# AK4493-Combi10.net
KiCad netlist of a schematic drawn in EAGLE
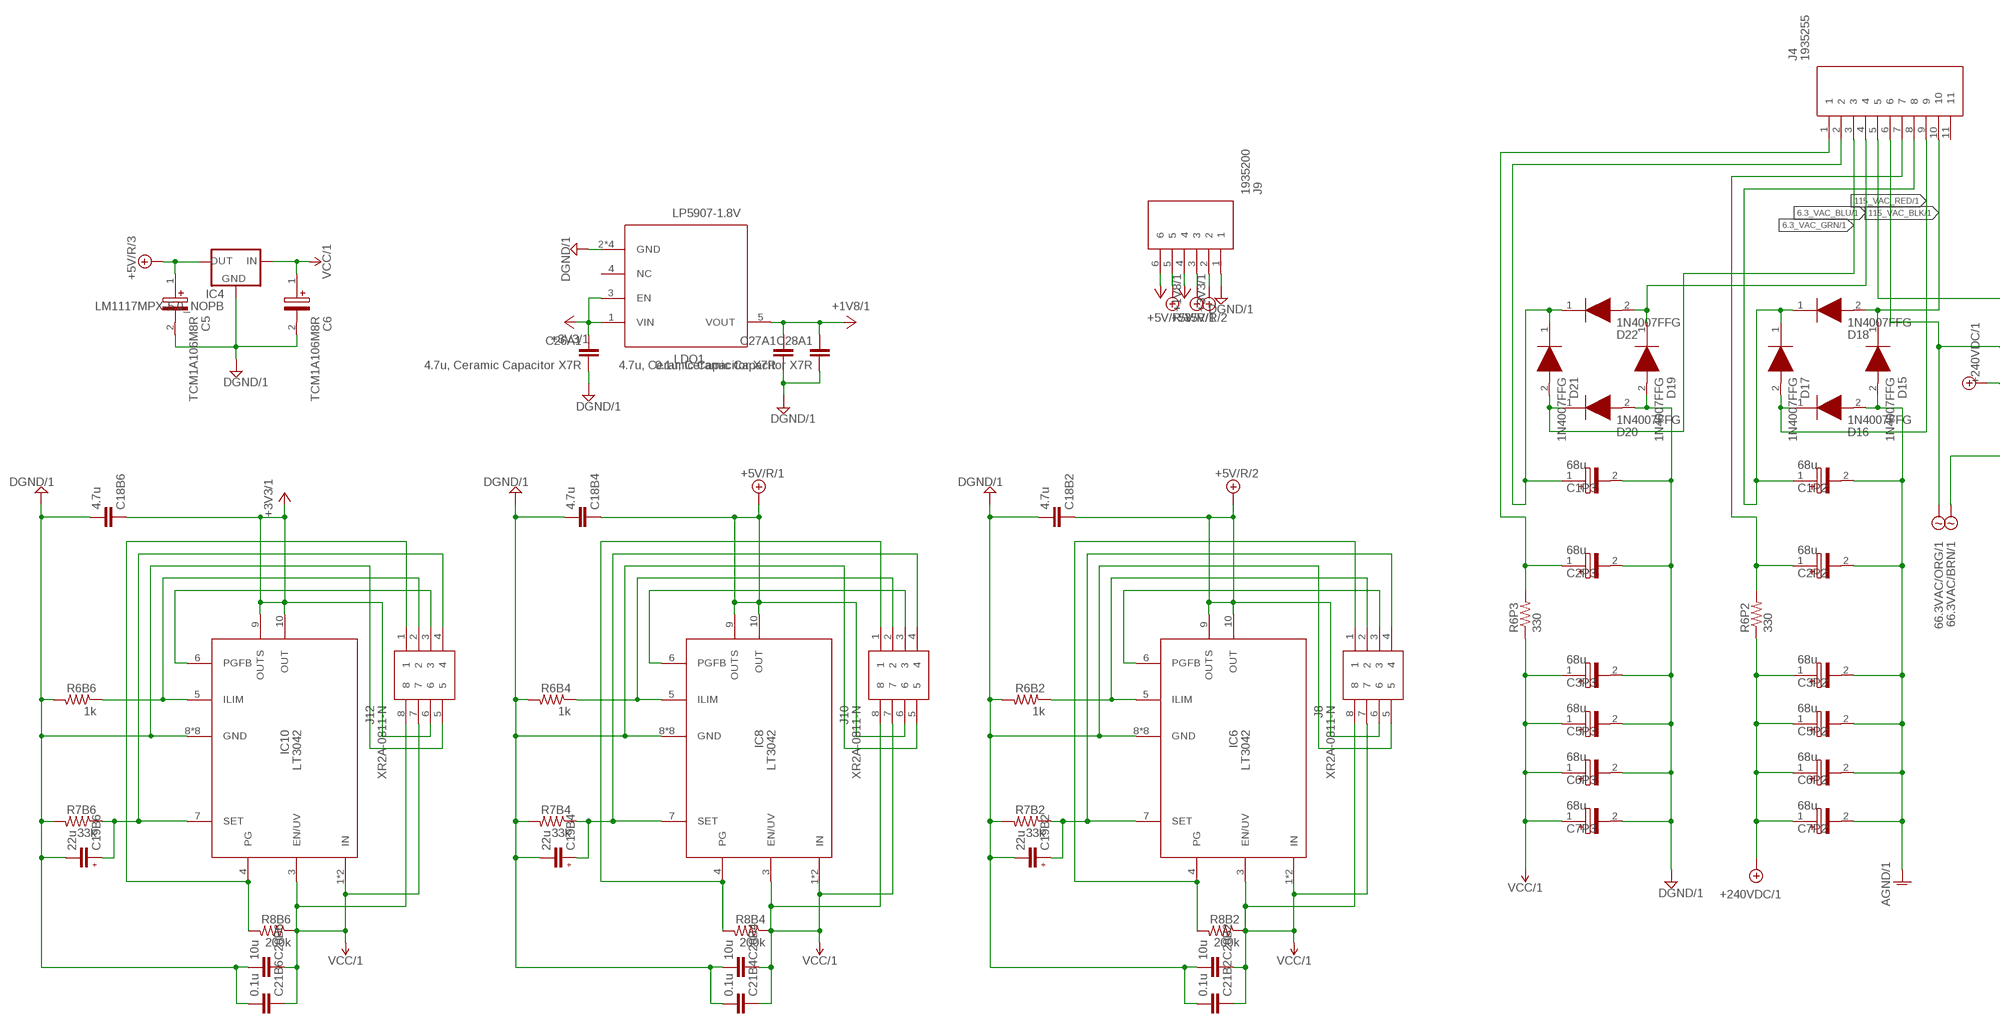
[diagram p0: schematic, sheet 1, part 1 of 3]
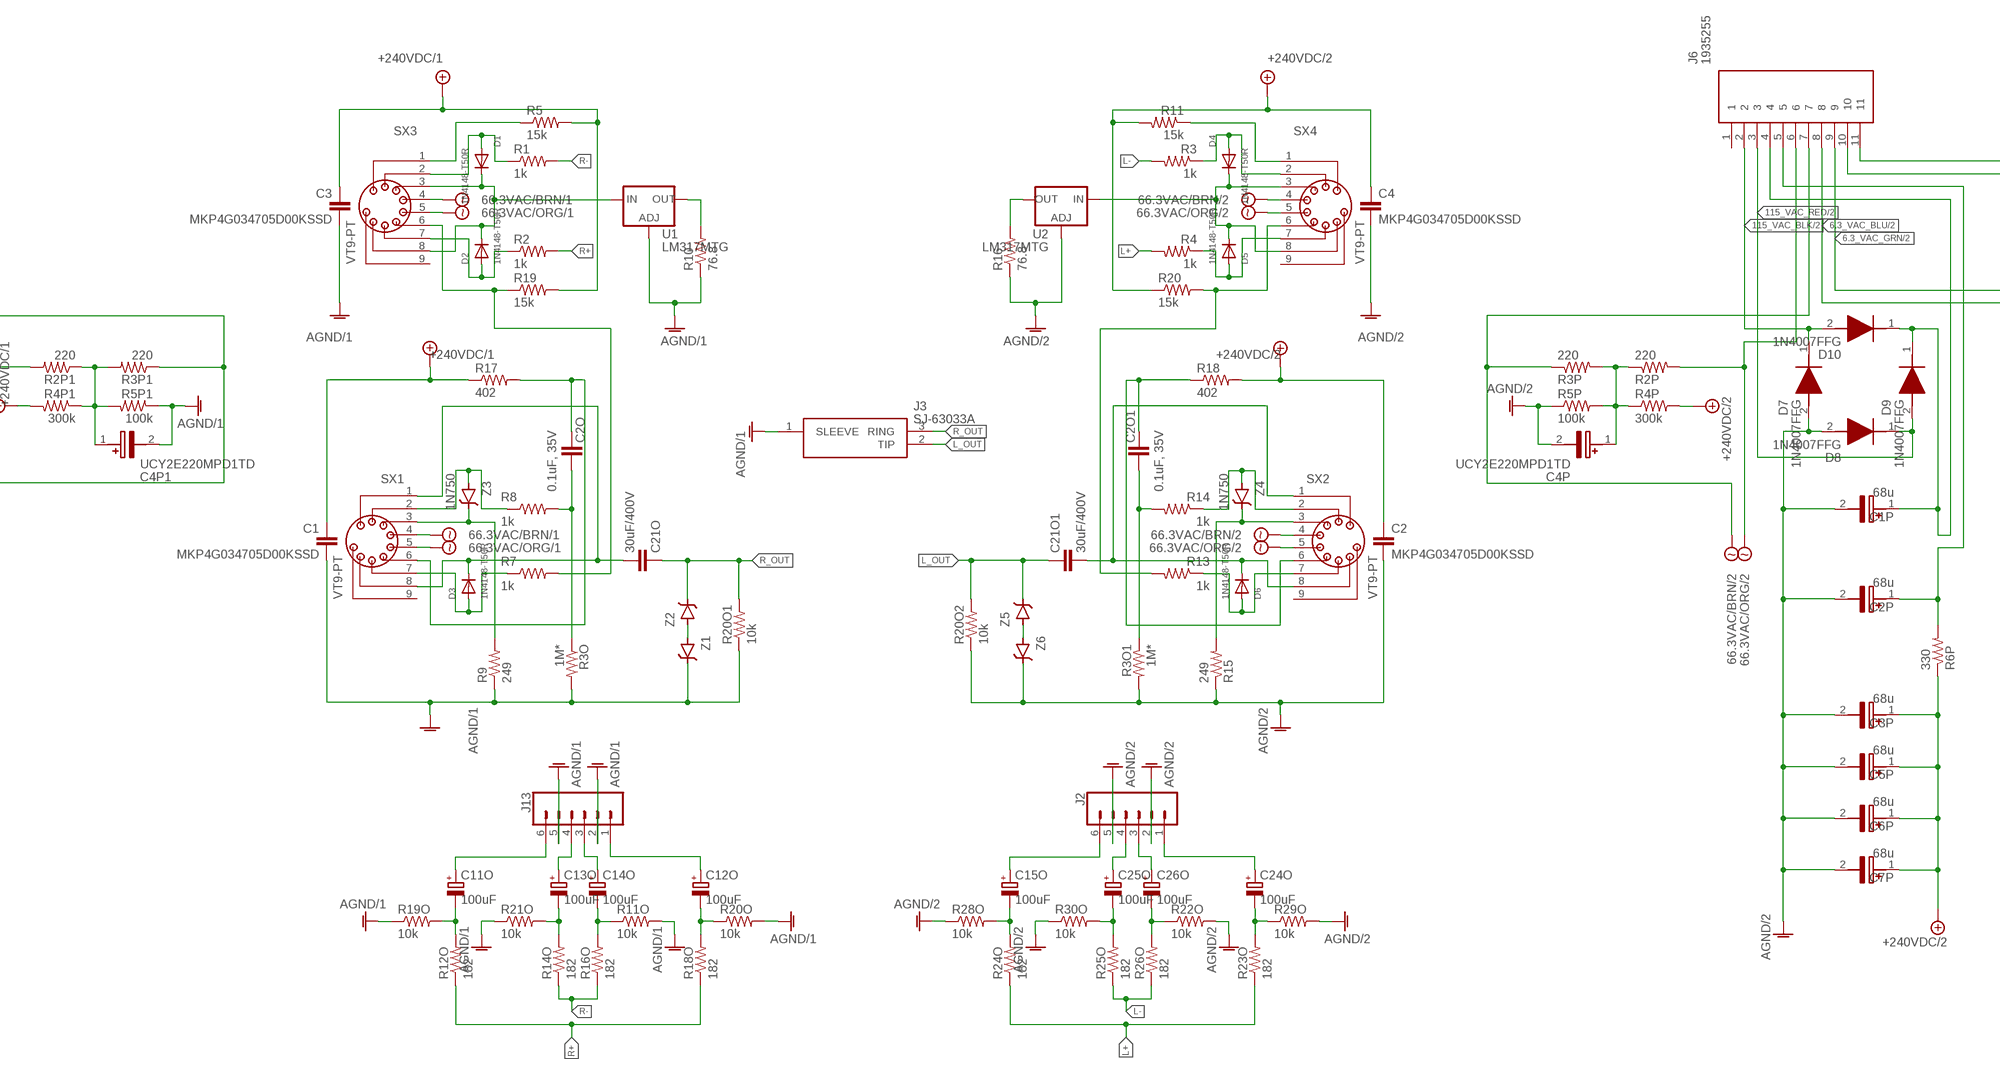
[diagram p1: schematic, sheet 1, part 2 of 3]
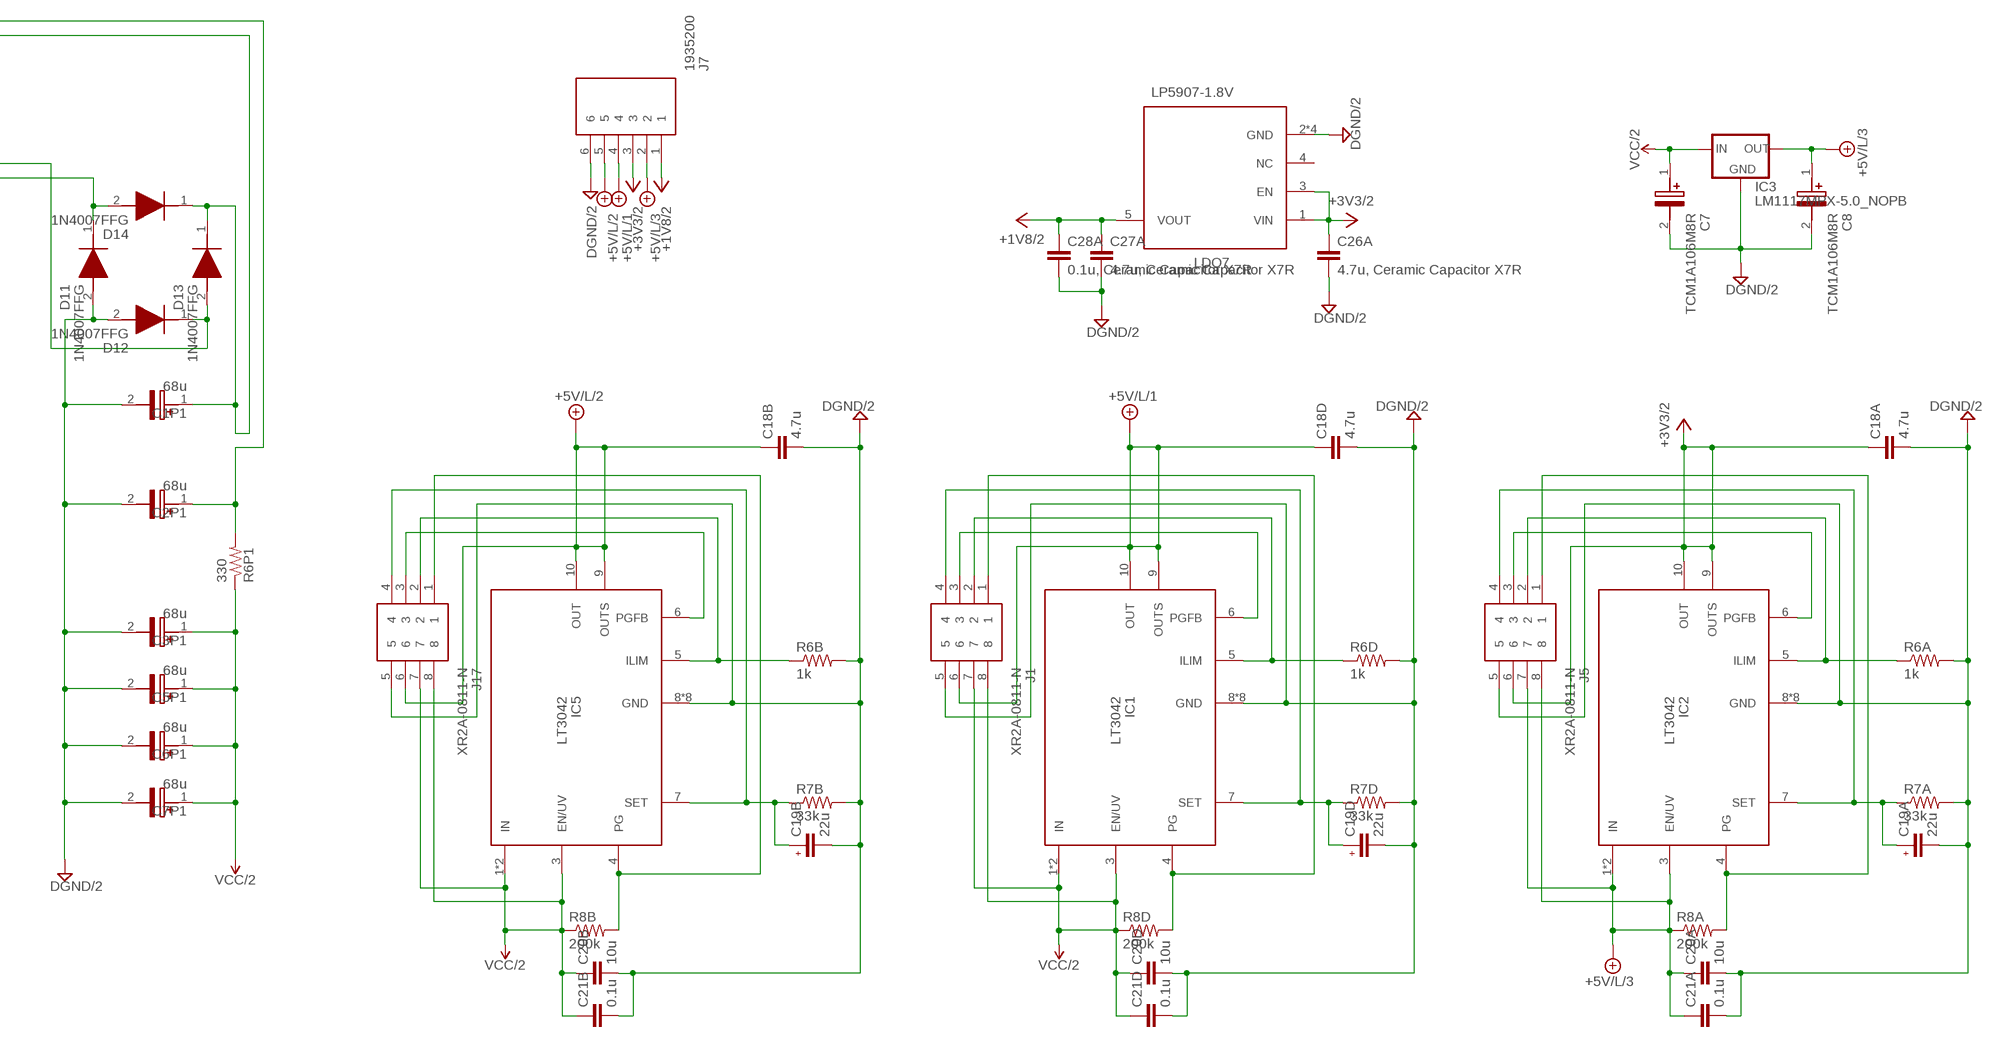
[diagram p2: schematic, sheet 1, part 3 of 3]

(export (version "E")
  (design (tool "Eeschema 10.0.6"))
  (components
    (comp (ref "C1")
      (value "MKP4G034705D00KSSD")
      (footprint "eagle-import:MKP4G034705D00KSSD")
      (fields (field (name "MOUSER_PART_NUMBER") "505-MKP4G034705DKSSD"))
      (libsource (lib "eagle-import") (part "MKP4G034705D00KSSD"))
    )
    (comp (ref "C1P")
      (value "68u")
      (footprint "eagle-import:CAPPRD750W80D1475H4700")
      (fields
        (field (name "MANUFACTURER_PART_NUMBER") "500HXW68MEFR14.5X45")
        (field (name "MOUSER_PART_NUMBER") "232-500HXW68MEFR145X")
      )
      (libsource (lib "eagle-import") (part "500HXW68MEFR14.5X45"))
    )
    (comp (ref "C1P1")
      (value "68u")
      (footprint "eagle-import:CAPPRD750W80D1475H4700")
      (fields
        (field (name "MANUFACTURER_PART_NUMBER") "500HXW68MEFR14.5X45")
        (field (name "MOUSER_PART_NUMBER") "232-500HXW68MEFR145X")
      )
      (libsource (lib "eagle-import") (part "500HXW68MEFR14.5X45"))
    )
    (comp (ref "C1P2")
      (value "68u")
      (footprint "eagle-import:CAPPRD750W80D1475H4700")
      (fields
        (field (name "MANUFACTURER_PART_NUMBER") "500HXW68MEFR14.5X45")
        (field (name "MOUSER_PART_NUMBER") "232-500HXW68MEFR145X")
      )
      (libsource (lib "eagle-import") (part "500HXW68MEFR14.5X45"))
    )
    (comp (ref "C1P3")
      (value "68u")
      (footprint "eagle-import:CAPPRD750W80D1475H4700")
      (fields
        (field (name "MANUFACTURER_PART_NUMBER") "500HXW68MEFR14.5X45")
        (field (name "MOUSER_PART_NUMBER") "232-500HXW68MEFR145X")
      )
      (libsource (lib "eagle-import") (part "500HXW68MEFR14.5X45"))
    )
    (comp (ref "C2")
      (value "MKP4G034705D00KSSD")
      (footprint "eagle-import:MKP4G034705D00KSSD")
      (fields (field (name "MOUSER_PART_NUMBER") "505-MKP4G034705DKSSD"))
      (libsource (lib "eagle-import") (part "MKP4G034705D00KSSD"))
    )
    (comp (ref "C2O")
      (value "0.1uF, 35V")
      (footprint "eagle-import:MKS4B031002A00JC00")
      (fields
        (field (name "MANUFACTURER_PART_NUMBER") "MKS4B031002A00JC00")
        (field (name "MOUSER_PART_NUMBER") "505-MKS4B0312AJC")
      )
      (libsource (lib "eagle-import") (part "MKS4B031002A00JC00"))
    )
    (comp (ref "C2O1")
      (value "0.1uF, 35V")
      (footprint "eagle-import:MKS4B031002A00JC00")
      (fields
        (field (name "MANUFACTURER_PART_NUMBER") "MKS4B031002A00JC00")
        (field (name "MOUSER_PART_NUMBER") "505-MKS4B0312AJC")
      )
      (libsource (lib "eagle-import") (part "MKS4B031002A00JC00"))
    )
    (comp (ref "C2P")
      (value "68u")
      (footprint "eagle-import:CAPPRD750W80D1475H4700")
      (fields
        (field (name "MANUFACTURER_PART_NUMBER") "500HXW68MEFR14.5X45")
        (field (name "MOUSER_PART_NUMBER") "232-500HXW68MEFR145X")
      )
      (libsource (lib "eagle-import") (part "500HXW68MEFR14.5X45"))
    )
    (comp (ref "C2P1")
      (value "68u")
      (footprint "eagle-import:CAPPRD750W80D1475H4700")
      (fields
        (field (name "MANUFACTURER_PART_NUMBER") "500HXW68MEFR14.5X45")
        (field (name "MOUSER_PART_NUMBER") "232-500HXW68MEFR145X")
      )
      (libsource (lib "eagle-import") (part "500HXW68MEFR14.5X45"))
    )
    (comp (ref "C2P2")
      (value "68u")
      (footprint "eagle-import:CAPPRD750W80D1475H4700")
      (fields
        (field (name "MANUFACTURER_PART_NUMBER") "500HXW68MEFR14.5X45")
        (field (name "MOUSER_PART_NUMBER") "232-500HXW68MEFR145X")
      )
      (libsource (lib "eagle-import") (part "500HXW68MEFR14.5X45"))
    )
    (comp (ref "C2P3")
      (value "68u")
      (footprint "eagle-import:CAPPRD750W80D1475H4700")
      (fields
        (field (name "MANUFACTURER_PART_NUMBER") "500HXW68MEFR14.5X45")
        (field (name "MOUSER_PART_NUMBER") "232-500HXW68MEFR145X")
      )
      (libsource (lib "eagle-import") (part "500HXW68MEFR14.5X45"))
    )
    (comp (ref "C3")
      (value "MKP4G034705D00KSSD")
      (footprint "eagle-import:MKP4G034705D00KSSD")
      (fields (field (name "MOUSER_PART_NUMBER") "505-MKP4G034705DKSSD"))
      (libsource (lib "eagle-import") (part "MKP4G034705D00KSSD"))
    )
    (comp (ref "C3P")
      (value "68u")
      (footprint "eagle-import:CAPPRD750W80D1475H4700")
      (fields
        (field (name "MANUFACTURER_PART_NUMBER") "500HXW68MEFR14.5X45")
        (field (name "MOUSER_PART_NUMBER") "232-500HXW68MEFR145X")
      )
      (libsource (lib "eagle-import") (part "500HXW68MEFR14.5X45"))
    )
    (comp (ref "C3P1")
      (value "68u")
      (footprint "eagle-import:CAPPRD750W80D1475H4700")
      (fields
        (field (name "MANUFACTURER_PART_NUMBER") "500HXW68MEFR14.5X45")
        (field (name "MOUSER_PART_NUMBER") "232-500HXW68MEFR145X")
      )
      (libsource (lib "eagle-import") (part "500HXW68MEFR14.5X45"))
    )
    (comp (ref "C3P2")
      (value "68u")
      (footprint "eagle-import:CAPPRD750W80D1475H4700")
      (fields
        (field (name "MANUFACTURER_PART_NUMBER") "500HXW68MEFR14.5X45")
        (field (name "MOUSER_PART_NUMBER") "232-500HXW68MEFR145X")
      )
      (libsource (lib "eagle-import") (part "500HXW68MEFR14.5X45"))
    )
    (comp (ref "C3P3")
      (value "68u")
      (footprint "eagle-import:CAPPRD750W80D1475H4700")
      (fields
        (field (name "MANUFACTURER_PART_NUMBER") "500HXW68MEFR14.5X45")
        (field (name "MOUSER_PART_NUMBER") "232-500HXW68MEFR145X")
      )
      (libsource (lib "eagle-import") (part "500HXW68MEFR14.5X45"))
    )
    (comp (ref "C4")
      (value "MKP4G034705D00KSSD")
      (footprint "eagle-import:MKP4G034705D00KSSD")
      (fields (field (name "MOUSER_PART_NUMBER") "505-MKP4G034705DKSSD"))
      (libsource (lib "eagle-import") (part "MKP4G034705D00KSSD"))
    )
    (comp (ref "C4P")
      (value "UCY2E220MPD1TD")
      (footprint "eagle-import:CAPPRD500W60D1025H1750")
      (fields (field (name "MOUSER_PART_NUMBER") "647-UCY2E220MPD1TD"))
      (libsource (lib "eagle-import") (part "UCY2E220MPD1TD"))
    )
    (comp (ref "C4P1")
      (value "UCY2E220MPD1TD")
      (footprint "eagle-import:CAPPRD500W60D1025H1750")
      (fields (field (name "MOUSER_PART_NUMBER") "647-UCY2E220MPD1TD"))
      (libsource (lib "eagle-import") (part "UCY2E220MPD1TD"))
    )
    (comp (ref "C5")
      (value "TCM1A106M8R")
      (footprint "eagle-import:CAPPM168X90N")
      (fields (field (name "MOUSER_PART_NUMBER") "755-TCM1A106M8R"))
      (libsource (lib "eagle-import") (part "TCM1A106M8R"))
    )
    (comp (ref "C5P")
      (value "68u")
      (footprint "eagle-import:CAPPRD750W80D1475H4700")
      (fields
        (field (name "MANUFACTURER_PART_NUMBER") "500HXW68MEFR14.5X45")
        (field (name "MOUSER_PART_NUMBER") "232-500HXW68MEFR145X")
      )
      (libsource (lib "eagle-import") (part "500HXW68MEFR14.5X45"))
    )
    (comp (ref "C5P1")
      (value "68u")
      (footprint "eagle-import:CAPPRD750W80D1475H4700")
      (fields
        (field (name "MANUFACTURER_PART_NUMBER") "500HXW68MEFR14.5X45")
        (field (name "MOUSER_PART_NUMBER") "232-500HXW68MEFR145X")
      )
      (libsource (lib "eagle-import") (part "500HXW68MEFR14.5X45"))
    )
    (comp (ref "C5P2")
      (value "68u")
      (footprint "eagle-import:CAPPRD750W80D1475H4700")
      (fields
        (field (name "MANUFACTURER_PART_NUMBER") "500HXW68MEFR14.5X45")
        (field (name "MOUSER_PART_NUMBER") "232-500HXW68MEFR145X")
      )
      (libsource (lib "eagle-import") (part "500HXW68MEFR14.5X45"))
    )
    (comp (ref "C5P3")
      (value "68u")
      (footprint "eagle-import:CAPPRD750W80D1475H4700")
      (fields
        (field (name "MANUFACTURER_PART_NUMBER") "500HXW68MEFR14.5X45")
        (field (name "MOUSER_PART_NUMBER") "232-500HXW68MEFR145X")
      )
      (libsource (lib "eagle-import") (part "500HXW68MEFR14.5X45"))
    )
    (comp (ref "C6")
      (value "TCM1A106M8R")
      (footprint "eagle-import:CAPPM168X90N")
      (fields (field (name "MOUSER_PART_NUMBER") "755-TCM1A106M8R"))
      (libsource (lib "eagle-import") (part "TCM1A106M8R"))
    )
    (comp (ref "C6P")
      (value "68u")
      (footprint "eagle-import:CAPPRD750W80D1475H4700")
      (fields
        (field (name "MANUFACTURER_PART_NUMBER") "500HXW68MEFR14.5X45")
        (field (name "MOUSER_PART_NUMBER") "232-500HXW68MEFR145X")
      )
      (libsource (lib "eagle-import") (part "500HXW68MEFR14.5X45"))
    )
    (comp (ref "C6P1")
      (value "68u")
      (footprint "eagle-import:CAPPRD750W80D1475H4700")
      (fields
        (field (name "MANUFACTURER_PART_NUMBER") "500HXW68MEFR14.5X45")
        (field (name "MOUSER_PART_NUMBER") "232-500HXW68MEFR145X")
      )
      (libsource (lib "eagle-import") (part "500HXW68MEFR14.5X45"))
    )
    (comp (ref "C6P2")
      (value "68u")
      (footprint "eagle-import:CAPPRD750W80D1475H4700")
      (fields
        (field (name "MANUFACTURER_PART_NUMBER") "500HXW68MEFR14.5X45")
        (field (name "MOUSER_PART_NUMBER") "232-500HXW68MEFR145X")
      )
      (libsource (lib "eagle-import") (part "500HXW68MEFR14.5X45"))
    )
    (comp (ref "C6P3")
      (value "68u")
      (footprint "eagle-import:CAPPRD750W80D1475H4700")
      (fields
        (field (name "MANUFACTURER_PART_NUMBER") "500HXW68MEFR14.5X45")
        (field (name "MOUSER_PART_NUMBER") "232-500HXW68MEFR145X")
      )
      (libsource (lib "eagle-import") (part "500HXW68MEFR14.5X45"))
    )
    (comp (ref "C7")
      (value "TCM1A106M8R")
      (footprint "eagle-import:CAPPM168X90N")
      (fields (field (name "MOUSER_PART_NUMBER") "755-TCM1A106M8R"))
      (libsource (lib "eagle-import") (part "TCM1A106M8R"))
    )
    (comp (ref "C7P")
      (value "68u")
      (footprint "eagle-import:CAPPRD750W80D1475H4700")
      (fields
        (field (name "MANUFACTURER_PART_NUMBER") "500HXW68MEFR14.5X45")
        (field (name "MOUSER_PART_NUMBER") "232-500HXW68MEFR145X")
      )
      (libsource (lib "eagle-import") (part "500HXW68MEFR14.5X45"))
    )
    (comp (ref "C7P1")
      (value "68u")
      (footprint "eagle-import:CAPPRD750W80D1475H4700")
      (fields
        (field (name "MANUFACTURER_PART_NUMBER") "500HXW68MEFR14.5X45")
        (field (name "MOUSER_PART_NUMBER") "232-500HXW68MEFR145X")
      )
      (libsource (lib "eagle-import") (part "500HXW68MEFR14.5X45"))
    )
    (comp (ref "C7P2")
      (value "68u")
      (footprint "eagle-import:CAPPRD750W80D1475H4700")
      (fields
        (field (name "MANUFACTURER_PART_NUMBER") "500HXW68MEFR14.5X45")
        (field (name "MOUSER_PART_NUMBER") "232-500HXW68MEFR145X")
      )
      (libsource (lib "eagle-import") (part "500HXW68MEFR14.5X45"))
    )
    (comp (ref "C7P3")
      (value "68u")
      (footprint "eagle-import:CAPPRD750W80D1475H4700")
      (fields
        (field (name "MANUFACTURER_PART_NUMBER") "500HXW68MEFR14.5X45")
        (field (name "MOUSER_PART_NUMBER") "232-500HXW68MEFR145X")
      )
      (libsource (lib "eagle-import") (part "500HXW68MEFR14.5X45"))
    )
    (comp (ref "C8")
      (value "TCM1A106M8R")
      (footprint "eagle-import:CAPPM168X90N")
      (fields (field (name "MOUSER_PART_NUMBER") "755-TCM1A106M8R"))
      (libsource (lib "eagle-import") (part "TCM1A106M8R"))
    )
    (comp (ref "C11O")
      (value "100uF")
      (footprint "eagle-import:CAPPRD350W60D825H1300")
      (fields
        (field (name "ARROW_PART_NUMBER") "UFW1H101MPD1TD")
        (field (name "MOUSER_PART_NUMBER") "647-UFW1H101MPD1TD")
      )
      (libsource (lib "eagle-import") (part "UFW1H101MPD1TD"))
    )
    (comp (ref "C12O")
      (value "100uF")
      (footprint "eagle-import:CAPPRD350W60D825H1300")
      (fields
        (field (name "ARROW_PART_NUMBER") "UFW1H101MPD1TD")
        (field (name "MOUSER_PART_NUMBER") "647-UFW1H101MPD1TD")
      )
      (libsource (lib "eagle-import") (part "UFW1H101MPD1TD"))
    )
    (comp (ref "C13O")
      (value "100uF")
      (footprint "eagle-import:CAPPRD350W60D825H1300")
      (fields
        (field (name "ARROW_PART_NUMBER") "UFW1H101MPD1TD")
        (field (name "MOUSER_PART_NUMBER") "647-UFW1H101MPD1TD")
      )
      (libsource (lib "eagle-import") (part "UFW1H101MPD1TD"))
    )
    (comp (ref "C14O")
      (value "100uF")
      (footprint "eagle-import:CAPPRD350W60D825H1300")
      (fields
        (field (name "ARROW_PART_NUMBER") "UFW1H101MPD1TD")
        (field (name "MOUSER_PART_NUMBER") "647-UFW1H101MPD1TD")
      )
      (libsource (lib "eagle-import") (part "UFW1H101MPD1TD"))
    )
    (comp (ref "C15O")
      (value "100uF")
      (footprint "eagle-import:CAPPRD350W60D825H1300")
      (fields
        (field (name "ARROW_PART_NUMBER") "UFW1H101MPD1TD")
        (field (name "MOUSER_PART_NUMBER") "647-UFW1H101MPD1TD")
      )
      (libsource (lib "eagle-import") (part "UFW1H101MPD1TD"))
    )
    (comp (ref "C18A")
      (value "4.7u")
      (footprint "eagle-import:CAPC2013X140N")
      (fields
        (field (name "MANUFACTURER_PART_NUMBER") "EMK212ABJ475KG-T")
        (field (name "MOUSER_PART_NUMBER") "963-EMK212ABJ475KG-T")
      )
      (libsource (lib "eagle-import") (part "EMK212ABJ475KG-T"))
    )
    (comp (ref "C18B")
      (value "4.7u")
      (footprint "eagle-import:CAPC2013X140N")
      (fields
        (field (name "MANUFACTURER_PART_NUMBER") "EMK212ABJ475KG-T")
        (field (name "MOUSER_PART_NUMBER") "963-EMK212ABJ475KG-T")
      )
      (libsource (lib "eagle-import") (part "EMK212ABJ475KG-T"))
    )
    (comp (ref "C18B2")
      (value "4.7u")
      (footprint "eagle-import:CAPC2013X140N")
      (fields
        (field (name "MANUFACTURER_PART_NUMBER") "EMK212ABJ475KG-T")
        (field (name "MOUSER_PART_NUMBER") "963-EMK212ABJ475KG-T")
      )
      (libsource (lib "eagle-import") (part "EMK212ABJ475KG-T"))
    )
    (comp (ref "C18B4")
      (value "4.7u")
      (footprint "eagle-import:CAPC2013X140N")
      (fields
        (field (name "MANUFACTURER_PART_NUMBER") "EMK212ABJ475KG-T")
        (field (name "MOUSER_PART_NUMBER") "963-EMK212ABJ475KG-T")
      )
      (libsource (lib "eagle-import") (part "EMK212ABJ475KG-T"))
    )
    (comp (ref "C18B6")
      (value "4.7u")
      (footprint "eagle-import:CAPC2013X140N")
      (fields
        (field (name "MANUFACTURER_PART_NUMBER") "EMK212ABJ475KG-T")
        (field (name "MOUSER_PART_NUMBER") "963-EMK212ABJ475KG-T")
      )
      (libsource (lib "eagle-import") (part "EMK212ABJ475KG-T"))
    )
    (comp (ref "C18D")
      (value "4.7u")
      (footprint "eagle-import:CAPC2013X140N")
      (fields
        (field (name "MANUFACTURER_PART_NUMBER") "EMK212ABJ475KG-T")
        (field (name "MOUSER_PART_NUMBER") "963-EMK212ABJ475KG-T")
      )
      (libsource (lib "eagle-import") (part "EMK212ABJ475KG-T"))
    )
    (comp (ref "C19A")
      (value "22u")
      (footprint "eagle-import:C1206")
      (fields
        (field (name "MANUFACTURER_PART_NUMBER") "EMK316BB7226ML-T")
        (field (name "MOUSER_PART_NUMBER") "963-EMK316BB7226ML-T")
      )
      (libsource (lib "eagle-import") (part "EMK316BB7226ML-T"))
    )
    (comp (ref "C19B")
      (value "22u")
      (footprint "eagle-import:C1206")
      (fields
        (field (name "MANUFACTURER_PART_NUMBER") "EMK316BB7226ML-T")
        (field (name "MOUSER_PART_NUMBER") "963-EMK316BB7226ML-T")
      )
      (libsource (lib "eagle-import") (part "EMK316BB7226ML-T"))
    )
    (comp (ref "C19B2")
      (value "22u")
      (footprint "eagle-import:C1206")
      (fields
        (field (name "MANUFACTURER_PART_NUMBER") "EMK316BB7226ML-T")
        (field (name "MOUSER_PART_NUMBER") "963-EMK316BB7226ML-T")
      )
      (libsource (lib "eagle-import") (part "EMK316BB7226ML-T"))
    )
    (comp (ref "C19B4")
      (value "22u")
      (footprint "eagle-import:C1206")
      (fields
        (field (name "MANUFACTURER_PART_NUMBER") "EMK316BB7226ML-T")
        (field (name "MOUSER_PART_NUMBER") "963-EMK316BB7226ML-T")
      )
      (libsource (lib "eagle-import") (part "EMK316BB7226ML-T"))
    )
    (comp (ref "C19B6")
      (value "22u")
      (footprint "eagle-import:C1206")
      (fields
        (field (name "MANUFACTURER_PART_NUMBER") "EMK316BB7226ML-T")
        (field (name "MOUSER_PART_NUMBER") "963-EMK316BB7226ML-T")
      )
      (libsource (lib "eagle-import") (part "EMK316BB7226ML-T"))
    )
    (comp (ref "C19D")
      (value "22u")
      (footprint "eagle-import:C1206")
      (fields
        (field (name "MANUFACTURER_PART_NUMBER") "EMK316BB7226ML-T")
        (field (name "MOUSER_PART_NUMBER") "963-EMK316BB7226ML-T")
      )
      (libsource (lib "eagle-import") (part "EMK316BB7226ML-T"))
    )
    (comp (ref "C20A")
      (value "10u")
      (footprint "eagle-import:CAPC2012X135N")
      (fields
        (field (name "MANUFACTURER_PART_NUMBER") "EMK212BB7106KG-T")
        (field (name "MOUSER_PART_NUMBER") "963-EMK212BB7106KG-T")
      )
      (libsource (lib "eagle-import") (part "EMK212BB7106KG-T"))
    )
    (comp (ref "C20B")
      (value "10u")
      (footprint "eagle-import:CAPC2012X135N")
      (fields
        (field (name "MANUFACTURER_PART_NUMBER") "EMK212BB7106KG-T")
        (field (name "MOUSER_PART_NUMBER") "963-EMK212BB7106KG-T")
      )
      (libsource (lib "eagle-import") (part "EMK212BB7106KG-T"))
    )
    (comp (ref "C20B2")
      (value "10u")
      (footprint "eagle-import:CAPC2012X135N")
      (fields
        (field (name "MANUFACTURER_PART_NUMBER") "EMK212BB7106KG-T")
        (field (name "MOUSER_PART_NUMBER") "963-EMK212BB7106KG-T")
      )
      (libsource (lib "eagle-import") (part "EMK212BB7106KG-T"))
    )
    (comp (ref "C20B4")
      (value "10u")
      (footprint "eagle-import:CAPC2012X135N")
      (fields
        (field (name "MANUFACTURER_PART_NUMBER") "EMK212BB7106KG-T")
        (field (name "MOUSER_PART_NUMBER") "963-EMK212BB7106KG-T")
      )
      (libsource (lib "eagle-import") (part "EMK212BB7106KG-T"))
    )
    (comp (ref "C20B6")
      (value "10u")
      (footprint "eagle-import:CAPC2012X135N")
      (fields
        (field (name "MANUFACTURER_PART_NUMBER") "EMK212BB7106KG-T")
        (field (name "MOUSER_PART_NUMBER") "963-EMK212BB7106KG-T")
      )
      (libsource (lib "eagle-import") (part "EMK212BB7106KG-T"))
    )
    (comp (ref "C20D")
      (value "10u")
      (footprint "eagle-import:CAPC2012X135N")
      (fields
        (field (name "MANUFACTURER_PART_NUMBER") "EMK212BB7106KG-T")
        (field (name "MOUSER_PART_NUMBER") "963-EMK212BB7106KG-T")
      )
      (libsource (lib "eagle-import") (part "EMK212BB7106KG-T"))
    )
    (comp (ref "C21A")
      (value "0.1u")
      (footprint "eagle-import:CAPC2012X135N")
      (fields
        (field (name "MANUFACTURER_PART_NUMBER") "EMF212B7104KGHT")
        (field (name "MOUSER_PART_NUMBER") "963-EMF212B7104KGHT")
      )
      (libsource (lib "eagle-import") (part "EMF212B7104KGHT"))
    )
    (comp (ref "C21B")
      (value "0.1u")
      (footprint "eagle-import:CAPC2012X135N")
      (fields
        (field (name "MANUFACTURER_PART_NUMBER") "EMF212B7104KGHT")
        (field (name "MOUSER_PART_NUMBER") "963-EMF212B7104KGHT")
      )
      (libsource (lib "eagle-import") (part "EMF212B7104KGHT"))
    )
    (comp (ref "C21B2")
      (value "0.1u")
      (footprint "eagle-import:CAPC2012X135N")
      (fields
        (field (name "MANUFACTURER_PART_NUMBER") "EMF212B7104KGHT")
        (field (name "MOUSER_PART_NUMBER") "963-EMF212B7104KGHT")
      )
      (libsource (lib "eagle-import") (part "EMF212B7104KGHT"))
    )
    (comp (ref "C21B4")
      (value "0.1u")
      (footprint "eagle-import:CAPC2012X135N")
      (fields
        (field (name "MANUFACTURER_PART_NUMBER") "EMF212B7104KGHT")
        (field (name "MOUSER_PART_NUMBER") "963-EMF212B7104KGHT")
      )
      (libsource (lib "eagle-import") (part "EMF212B7104KGHT"))
    )
    (comp (ref "C21B6")
      (value "0.1u")
      (footprint "eagle-import:CAPC2012X135N")
      (fields
        (field (name "MANUFACTURER_PART_NUMBER") "EMF212B7104KGHT")
        (field (name "MOUSER_PART_NUMBER") "963-EMF212B7104KGHT")
      )
      (libsource (lib "eagle-import") (part "EMF212B7104KGHT"))
    )
    (comp (ref "C21D")
      (value "0.1u")
      (footprint "eagle-import:CAPC2012X135N")
      (fields
        (field (name "MANUFACTURER_PART_NUMBER") "EMF212B7104KGHT")
        (field (name "MOUSER_PART_NUMBER") "963-EMF212B7104KGHT")
      )
      (libsource (lib "eagle-import") (part "EMF212B7104KGHT"))
    )
    (comp (ref "C21O")
      (value "30uF/400V")
      (footprint "eagle-import:DCP4G056007GD4KSSD")
      (fields
        (field (name "MANUFACTURER_PART_NUMBER") "DCP4G056007GD4KSSD")
        (field (name "MOUSER_PART_NUMBER") "505-DCP4G056007GD4KS")
      )
      (libsource (lib "eagle-import") (part "DCP4G056007GD4KSSD"))
    )
    (comp (ref "C21O1")
      (value "30uF/400V")
      (footprint "eagle-import:DCP4G056007GD4KSSD")
      (fields
        (field (name "MANUFACTURER_PART_NUMBER") "DCP4G056007GD4KSSD")
        (field (name "MOUSER_PART_NUMBER") "505-DCP4G056007GD4KS")
      )
      (libsource (lib "eagle-import") (part "DCP4G056007GD4KSSD"))
    )
    (comp (ref "C24O")
      (value "100uF")
      (footprint "eagle-import:CAPPRD350W60D825H1300")
      (fields
        (field (name "ARROW_PART_NUMBER") "UFW1H101MPD1TD")
        (field (name "MOUSER_PART_NUMBER") "647-UFW1H101MPD1TD")
      )
      (libsource (lib "eagle-import") (part "UFW1H101MPD1TD"))
    )
    (comp (ref "C25O")
      (value "100uF")
      (footprint "eagle-import:CAPPRD350W60D825H1300")
      (fields
        (field (name "ARROW_PART_NUMBER") "UFW1H101MPD1TD")
        (field (name "MOUSER_PART_NUMBER") "647-UFW1H101MPD1TD")
      )
      (libsource (lib "eagle-import") (part "UFW1H101MPD1TD"))
    )
    (comp (ref "C26A")
      (value "4.7u, Ceramic Capacitor X7R")
      (footprint "eagle-import:CAPC2013X140N")
      (fields
        (field (name "MANUFACTURER_PART_NUMBER") "EMK212ABJ475KG-T")
        (field (name "MOUSER_PART_NUMBER") "963-EMK212ABJ475KG-T")
      )
      (libsource (lib "eagle-import") (part "EMK212ABJ475KG-T"))
    )
    (comp (ref "C26A1")
      (value "4.7u, Ceramic Capacitor X7R")
      (footprint "eagle-import:CAPC2013X140N")
      (fields
        (field (name "MANUFACTURER_PART_NUMBER") "EMK212ABJ475KG-T")
        (field (name "MOUSER_PART_NUMBER") "963-EMK212ABJ475KG-T")
      )
      (libsource (lib "eagle-import") (part "EMK212ABJ475KG-T"))
    )
    (comp (ref "C26O")
      (value "100uF")
      (footprint "eagle-import:CAPPRD350W60D825H1300")
      (fields
        (field (name "ARROW_PART_NUMBER") "UFW1H101MPD1TD")
        (field (name "MOUSER_PART_NUMBER") "647-UFW1H101MPD1TD")
      )
      (libsource (lib "eagle-import") (part "UFW1H101MPD1TD"))
    )
    (comp (ref "C27A")
      (value "4.7u, Ceramic Capacitor X7R")
      (footprint "eagle-import:CAPC2013X140N")
      (fields
        (field (name "MANUFACTURER_PART_NUMBER") "EMK212ABJ475KG-T")
        (field (name "MOUSER_PART_NUMBER") "963-EMK212ABJ475KG-T")
      )
      (libsource (lib "eagle-import") (part "EMK212ABJ475KG-T"))
    )
    (comp (ref "C27A1")
      (value "4.7u, Ceramic Capacitor X7R")
      (footprint "eagle-import:CAPC2013X140N")
      (fields
        (field (name "MANUFACTURER_PART_NUMBER") "EMK212ABJ475KG-T")
        (field (name "MOUSER_PART_NUMBER") "963-EMK212ABJ475KG-T")
      )
      (libsource (lib "eagle-import") (part "EMK212ABJ475KG-T"))
    )
    (comp (ref "C28A")
      (value "0.1u, Ceramic Capacitor X7R")
      (footprint "eagle-import:CAPC2012X135N")
      (fields
        (field (name "MANUFACTURER_PART_NUMBER") "EMF212B7104KGHT")
        (field (name "MOUSER_PART_NUMBER") "963-EMF212B7104KGHT")
      )
      (libsource (lib "eagle-import") (part "EMF212B7104KGHT"))
    )
    (comp (ref "C28A1")
      (value "0.1u, Ceramic Capacitor X7R")
      (footprint "eagle-import:CAPC2012X135N")
      (fields
        (field (name "MANUFACTURER_PART_NUMBER") "EMF212B7104KGHT")
        (field (name "MOUSER_PART_NUMBER") "963-EMF212B7104KGHT")
      )
      (libsource (lib "eagle-import") (part "EMF212B7104KGHT"))
    )
    (comp (ref "D1")
      (value "1N4148-T50R")
      (footprint "eagle-import:DIOAD1068W53L380D172")
      (fields (field (name "MOUSER_PART_NUMBER") "512-1N4148T50R"))
      (libsource (lib "eagle-import") (part "1N4148-T50R"))
    )
    (comp (ref "D2")
      (value "1N4148-T50R")
      (footprint "eagle-import:DIOAD1068W53L380D172")
      (fields (field (name "MOUSER_PART_NUMBER") "512-1N4148T50R"))
      (libsource (lib "eagle-import") (part "1N4148-T50R"))
    )
    (comp (ref "D3")
      (value "1N4148-T50R")
      (footprint "eagle-import:DIOAD1068W53L380D172")
      (fields (field (name "MOUSER_PART_NUMBER") "512-1N4148T50R"))
      (libsource (lib "eagle-import") (part "1N4148-T50R"))
    )
    (comp (ref "D4")
      (value "1N4148-T50R")
      (footprint "eagle-import:DIOAD1068W53L380D172")
      (fields (field (name "MOUSER_PART_NUMBER") "512-1N4148T50R"))
      (libsource (lib "eagle-import") (part "1N4148-T50R"))
    )
    (comp (ref "D5")
      (value "1N4148-T50R")
      (footprint "eagle-import:DIOAD1068W53L380D172")
      (fields (field (name "MOUSER_PART_NUMBER") "512-1N4148T50R"))
      (libsource (lib "eagle-import") (part "1N4148-T50R"))
    )
    (comp (ref "D6")
      (value "1N4148-T50R")
      (footprint "eagle-import:DIOAD1068W53L380D172")
      (fields (field (name "MOUSER_PART_NUMBER") "512-1N4148T50R"))
      (libsource (lib "eagle-import") (part "1N4148-T50R"))
    )
    (comp (ref "D7")
      (value "1N4007FFG")
      (footprint "eagle-import:DIOAD1405W86L465D235")
      (fields (field (name "MOUSER_PART_NUMBER") "863-1N4007FFG"))
      (libsource (lib "eagle-import") (part "1N4007FFG"))
    )
    (comp (ref "D8")
      (value "1N4007FFG")
      (footprint "eagle-import:DIOAD1405W86L465D235")
      (fields (field (name "MOUSER_PART_NUMBER") "863-1N4007FFG"))
      (libsource (lib "eagle-import") (part "1N4007FFG"))
    )
    (comp (ref "D9")
      (value "1N4007FFG")
      (footprint "eagle-import:DIOAD1405W86L465D235")
      (fields (field (name "MOUSER_PART_NUMBER") "863-1N4007FFG"))
      (libsource (lib "eagle-import") (part "1N4007FFG"))
    )
    (comp (ref "D10")
      (value "1N4007FFG")
      (footprint "eagle-import:DIOAD1405W86L465D235")
      (fields (field (name "MOUSER_PART_NUMBER") "863-1N4007FFG"))
      (libsource (lib "eagle-import") (part "1N4007FFG"))
    )
    (comp (ref "D11")
      (value "1N4007FFG")
      (footprint "eagle-import:DIOAD1405W86L465D235")
      (fields (field (name "MOUSER_PART_NUMBER") "863-1N4007FFG"))
      (libsource (lib "eagle-import") (part "1N4007FFG"))
    )
    (comp (ref "D12")
      (value "1N4007FFG")
      (footprint "eagle-import:DIOAD1405W86L465D235")
      (fields (field (name "MOUSER_PART_NUMBER") "863-1N4007FFG"))
      (libsource (lib "eagle-import") (part "1N4007FFG"))
    )
    (comp (ref "D13")
      (value "1N4007FFG")
      (footprint "eagle-import:DIOAD1405W86L465D235")
      (fields (field (name "MOUSER_PART_NUMBER") "863-1N4007FFG"))
      (libsource (lib "eagle-import") (part "1N4007FFG"))
    )
    (comp (ref "D14")
      (value "1N4007FFG")
      (footprint "eagle-import:DIOAD1405W86L465D235")
      (fields (field (name "MOUSER_PART_NUMBER") "863-1N4007FFG"))
      (libsource (lib "eagle-import") (part "1N4007FFG"))
    )
    (comp (ref "D15")
      (value "1N4007FFG")
      (footprint "eagle-import:DIOAD1405W86L465D235")
      (fields (field (name "MOUSER_PART_NUMBER") "863-1N4007FFG"))
      (libsource (lib "eagle-import") (part "1N4007FFG"))
    )
    (comp (ref "D16")
      (value "1N4007FFG")
      (footprint "eagle-import:DIOAD1405W86L465D235")
      (fields (field (name "MOUSER_PART_NUMBER") "863-1N4007FFG"))
      (libsource (lib "eagle-import") (part "1N4007FFG"))
    )
    (comp (ref "D17")
      (value "1N4007FFG")
      (footprint "eagle-import:DIOAD1405W86L465D235")
      (fields (field (name "MOUSER_PART_NUMBER") "863-1N4007FFG"))
      (libsource (lib "eagle-import") (part "1N4007FFG"))
    )
    (comp (ref "D18")
      (value "1N4007FFG")
      (footprint "eagle-import:DIOAD1405W86L465D235")
      (fields (field (name "MOUSER_PART_NUMBER") "863-1N4007FFG"))
      (libsource (lib "eagle-import") (part "1N4007FFG"))
    )
    (comp (ref "D19")
      (value "1N4007FFG")
      (footprint "eagle-import:DIOAD1405W86L465D235")
      (fields (field (name "MOUSER_PART_NUMBER") "863-1N4007FFG"))
      (libsource (lib "eagle-import") (part "1N4007FFG"))
    )
    (comp (ref "D20")
      (value "1N4007FFG")
      (footprint "eagle-import:DIOAD1405W86L465D235")
      (fields (field (name "MOUSER_PART_NUMBER") "863-1N4007FFG"))
      (libsource (lib "eagle-import") (part "1N4007FFG"))
    )
    (comp (ref "D21")
      (value "1N4007FFG")
      (footprint "eagle-import:DIOAD1405W86L465D235")
      (fields (field (name "MOUSER_PART_NUMBER") "863-1N4007FFG"))
      (libsource (lib "eagle-import") (part "1N4007FFG"))
    )
    (comp (ref "D22")
      (value "1N4007FFG")
      (footprint "eagle-import:DIOAD1405W86L465D235")
      (fields (field (name "MOUSER_PART_NUMBER") "863-1N4007FFG"))
      (libsource (lib "eagle-import") (part "1N4007FFG"))
    )
    (comp (ref "IC1")
      (value "LT3042")
      (footprint "eagle-import:SOP50P490X110-11N")
      (fields
        (field (name "MANUFACTURER_PART_NUMBER") "LT3042EMSE#PBF")
        (field (name "MOUSER_PART_NUMBER") "584-LT3042EMSE#PBF")
      )
      (libsource (lib "eagle-import") (part "LT3042"))
    )
    (comp (ref "IC2")
      (value "LT3042")
      (footprint "eagle-import:SOP50P490X110-11N")
      (fields
        (field (name "MANUFACTURER_PART_NUMBER") "LT3042EMSE#PBF")
        (field (name "MOUSER_PART_NUMBER") "584-LT3042EMSE#PBF")
      )
      (libsource (lib "eagle-import") (part "LT3042"))
    )
    (comp (ref "IC3")
      (value "LM1117MPX-5.0_NOPB")
      (footprint "eagle-import:SOT230P700X180-4N")
      (fields
        (field (name "MANUFACTURER_PART_NUMBER") "LM1117MPX-5.0/NOPB")
        (field (name "MOUSER_PART_NUMBER") "926-LM1117MPX5.0NOPB")
      )
      (libsource (lib "eagle-import") (part "LM1117MPX-5.0_NOPB"))
    )
    (comp (ref "IC4")
      (value "LM1117MPX-5.0_NOPB")
      (footprint "eagle-import:SOT230P700X180-4N")
      (fields
        (field (name "MANUFACTURER_PART_NUMBER") "LM1117MPX-5.0/NOPB")
        (field (name "MOUSER_PART_NUMBER") "926-LM1117MPX5.0NOPB")
      )
      (libsource (lib "eagle-import") (part "LM1117MPX-5.0_NOPB"))
    )
    (comp (ref "IC5")
      (value "LT3042")
      (footprint "eagle-import:SOP50P490X110-11N")
      (fields
        (field (name "MANUFACTURER_PART_NUMBER") "LT3042EMSE#PBF")
        (field (name "MOUSER_PART_NUMBER") "584-LT3042EMSE#PBF")
      )
      (libsource (lib "eagle-import") (part "LT3042"))
    )
    (comp (ref "IC6")
      (value "LT3042")
      (footprint "eagle-import:SOP50P490X110-11N")
      (fields
        (field (name "MANUFACTURER_PART_NUMBER") "LT3042EMSE#PBF")
        (field (name "MOUSER_PART_NUMBER") "584-LT3042EMSE#PBF")
      )
      (libsource (lib "eagle-import") (part "LT3042"))
    )
    (comp (ref "IC8")
      (value "LT3042")
      (footprint "eagle-import:SOP50P490X110-11N")
      (fields
        (field (name "MANUFACTURER_PART_NUMBER") "LT3042EMSE#PBF")
        (field (name "MOUSER_PART_NUMBER") "584-LT3042EMSE#PBF")
      )
      (libsource (lib "eagle-import") (part "LT3042"))
    )
    (comp (ref "IC10")
      (value "LT3042")
      (footprint "eagle-import:SOP50P490X110-11N")
      (fields
        (field (name "MANUFACTURER_PART_NUMBER") "LT3042EMSE#PBF")
        (field (name "MOUSER_PART_NUMBER") "584-LT3042EMSE#PBF")
      )
      (libsource (lib "eagle-import") (part "LT3042"))
    )
    (comp (ref "J1")
      (value "XR2A-0811-N")
      (footprint "eagle-import:DIPS762W51P254L1016H390Q8N")
      (fields (field (name "MOUSER_PART_NUMBER") "653-XR2A-0811-N"))
      (libsource (lib "eagle-import") (part "XR2A-0811-N"))
    )
    (comp (ref "J2")
      (value "CONN_06SILK_FEMALE_PTH")
      (footprint "eagle-import:1X06")
      (libsource (lib "eagle-import") (part "CONN_06SILK_FEMALE_PTH"))
    )
    (comp (ref "J3")
      (value "SJ-63033A")
      (footprint "eagle-import:SJ63033A")
      (libsource (lib "eagle-import") (part "SJ-63033A"))
    )
    (comp (ref "J4")
      (value "1935255")
      (footprint "eagle-import:1935255")
      (fields (field (name "MOUSER_PART_NUMBER") "651-1935255"))
      (libsource (lib "eagle-import") (part "1935255"))
    )
    (comp (ref "J5")
      (value "XR2A-0811-N")
      (footprint "eagle-import:DIPS762W51P254L1016H390Q8N")
      (fields (field (name "MOUSER_PART_NUMBER") "653-XR2A-0811-N"))
      (libsource (lib "eagle-import") (part "XR2A-0811-N"))
    )
    (comp (ref "J6")
      (value "1935255")
      (footprint "eagle-import:1935255")
      (fields (field (name "MOUSER_PART_NUMBER") "651-1935255"))
      (libsource (lib "eagle-import") (part "1935255"))
    )
    (comp (ref "J7")
      (value "1935200")
      (footprint "eagle-import:1935200")
      (fields (field (name "MOUSER_PART_NUMBER") "651-1935200"))
      (libsource (lib "eagle-import") (part "1935200"))
    )
    (comp (ref "J8")
      (value "XR2A-0811-N")
      (footprint "eagle-import:DIPS762W51P254L1016H390Q8N")
      (fields (field (name "MOUSER_PART_NUMBER") "653-XR2A-0811-N"))
      (libsource (lib "eagle-import") (part "XR2A-0811-N"))
    )
    (comp (ref "J9")
      (value "1935200")
      (footprint "eagle-import:1935200")
      (fields (field (name "MOUSER_PART_NUMBER") "651-1935200"))
      (libsource (lib "eagle-import") (part "1935200"))
    )
    (comp (ref "J10")
      (value "XR2A-0811-N")
      (footprint "eagle-import:DIPS762W51P254L1016H390Q8N")
      (fields (field (name "MOUSER_PART_NUMBER") "653-XR2A-0811-N"))
      (libsource (lib "eagle-import") (part "XR2A-0811-N"))
    )
    (comp (ref "J12")
      (value "XR2A-0811-N")
      (footprint "eagle-import:DIPS762W51P254L1016H390Q8N")
      (fields (field (name "MOUSER_PART_NUMBER") "653-XR2A-0811-N"))
      (libsource (lib "eagle-import") (part "XR2A-0811-N"))
    )
    (comp (ref "J13")
      (value "CONN_06SILK_FEMALE_PTH")
      (footprint "eagle-import:1X06")
      (libsource (lib "eagle-import") (part "CONN_06SILK_FEMALE_PTH"))
    )
    (comp (ref "J17")
      (value "XR2A-0811-N")
      (footprint "eagle-import:DIPS762W51P254L1016H390Q8N")
      (fields (field (name "MOUSER_PART_NUMBER") "653-XR2A-0811-N"))
      (libsource (lib "eagle-import") (part "XR2A-0811-N"))
    )
    (comp (ref "LDO1")
      (value "LP5907-1.8V")
      (footprint "eagle-import:SOT95P280X145-5N")
      (fields
        (field (name "ARROW_PART_NUMBER") "LP5907MFX-1.8/NOPB")
        (field (name "MOUSER_PART_NUMBER") "595-LP5907MFX-1.8NPB")
      )
      (libsource (lib "eagle-import") (part "LP5907-1.8V"))
    )
    (comp (ref "LDO7")
      (value "LP5907-1.8V")
      (footprint "eagle-import:SOT95P280X145-5N")
      (fields
        (field (name "ARROW_PART_NUMBER") "LP5907MFX-1.8/NOPB")
        (field (name "MOUSER_PART_NUMBER") "595-LP5907MFX-1.8NPB")
      )
      (libsource (lib "eagle-import") (part "LP5907-1.8V"))
    )
    (comp (ref "R1")
      (value "1k")
      (footprint "eagle-import:0207_10")
      (fields
        (field (name "MANUFACTURER_PART_NUMBER") "LR1F1K0")
        (field (name "MOUSER_PART_NUMBER") "279-LR1F1K0")
      )
      (libsource (lib "eagle-import") (part "LR1F1K0"))
    )
    (comp (ref "R2")
      (value "1k")
      (footprint "eagle-import:0207_10")
      (fields
        (field (name "MANUFACTURER_PART_NUMBER") "LR1F1K0")
        (field (name "MOUSER_PART_NUMBER") "279-LR1F1K0")
      )
      (libsource (lib "eagle-import") (part "LR1F1K0"))
    )
    (comp (ref "R2P")
      (value "220")
      (footprint "eagle-import:0411_15")
      (fields
        (field (name "MANUFACTURER_PART_NUMBER") "PR02000202200JA100")
        (field (name "MOUSER_PART_NUMBER") "594-5083NW220R0JA100")
      )
      (libsource (lib "eagle-import") (part "PR02000202200JA1000411/15"))
    )
    (comp (ref "R2P1")
      (value "220")
      (footprint "eagle-import:0411_15")
      (fields
        (field (name "MANUFACTURER_PART_NUMBER") "PR02000202200JA100")
        (field (name "MOUSER_PART_NUMBER") "594-5083NW220R0JA100")
      )
      (libsource (lib "eagle-import") (part "PR02000202200JA1000411/15"))
    )
    (comp (ref "R3")
      (value "1k")
      (footprint "eagle-import:0207_10")
      (fields
        (field (name "MANUFACTURER_PART_NUMBER") "LR1F1K0")
        (field (name "MOUSER_PART_NUMBER") "279-LR1F1K0")
      )
      (libsource (lib "eagle-import") (part "LR1F1K0"))
    )
    (comp (ref "R3O")
      (value "1M*")
      (footprint "eagle-import:0207_10")
      (fields
        (field (name "MANUFACTURER_PART_NUMBER") "LR1F1M0")
        (field (name "MOUSER_PART_NUMBER") "279-LR1F1M0")
      )
      (libsource (lib "eagle-import") (part "LR1F1M0"))
    )
    (comp (ref "R3O1")
      (value "1M*")
      (footprint "eagle-import:0207_10")
      (fields
        (field (name "MANUFACTURER_PART_NUMBER") "LR1F1M0")
        (field (name "MOUSER_PART_NUMBER") "279-LR1F1M0")
      )
      (libsource (lib "eagle-import") (part "LR1F1M0"))
    )
    (comp (ref "R3P")
      (value "220")
      (footprint "eagle-import:0411_15")
      (fields
        (field (name "MANUFACTURER_PART_NUMBER") "PR02000202200JA100")
        (field (name "MOUSER_PART_NUMBER") "594-5083NW220R0JA100")
      )
      (libsource (lib "eagle-import") (part "PR02000202200JA1000411/15"))
    )
    (comp (ref "R3P1")
      (value "220")
      (footprint "eagle-import:0411_15")
      (fields
        (field (name "MANUFACTURER_PART_NUMBER") "PR02000202200JA100")
        (field (name "MOUSER_PART_NUMBER") "594-5083NW220R0JA100")
      )
      (libsource (lib "eagle-import") (part "PR02000202200JA1000411/15"))
    )
    (comp (ref "R4")
      (value "1k")
      (footprint "eagle-import:0207_10")
      (fields
        (field (name "MANUFACTURER_PART_NUMBER") "LR1F1K0")
        (field (name "MOUSER_PART_NUMBER") "279-LR1F1K0")
      )
      (libsource (lib "eagle-import") (part "LR1F1K0"))
    )
    (comp (ref "R4P")
      (value "300k")
      (footprint "eagle-import:0411_15")
      (fields
        (field (name "MANUFACTURER_PART_NUMBER") "PR02000203003JR500")
        (field (name "MOUSER_PART_NUMBER") "594-5083NW300K0J")
      )
      (libsource (lib "eagle-import") (part "PR02000203003JR5000411/15"))
    )
    (comp (ref "R4P1")
      (value "300k")
      (footprint "eagle-import:0411_15")
      (fields
        (field (name "MANUFACTURER_PART_NUMBER") "PR02000203003JR500")
        (field (name "MOUSER_PART_NUMBER") "594-5083NW300K0J")
      )
      (libsource (lib "eagle-import") (part "PR02000203003JR5000411/15"))
    )
    (comp (ref "R5")
      (value "15k")
      (footprint "eagle-import:0411_15")
      (fields
        (field (name "MANUFACTURER_PART_NUMBER") "CPF215K000FKE14")
        (field (name "MOUSER_PART_NUMBER") "71-CPF2-F-15K-E3")
      )
      (libsource (lib "eagle-import") (part "CPF215K000FKE14"))
    )
    (comp (ref "R5P")
      (value "100k")
      (footprint "eagle-import:0411_15")
      (fields
        (field (name "MANUFACTURER_PART_NUMBER") "PR02000201003JA100")
        (field (name "MOUSER_PART_NUMBER") "594-5083NW100K0JA100")
      )
      (libsource (lib "eagle-import") (part "PR02000201003JA1000411/15"))
    )
    (comp (ref "R5P1")
      (value "100k")
      (footprint "eagle-import:0411_15")
      (fields
        (field (name "MANUFACTURER_PART_NUMBER") "PR02000201003JA100")
        (field (name "MOUSER_PART_NUMBER") "594-5083NW100K0JA100")
      )
      (libsource (lib "eagle-import") (part "PR02000201003JA1000411/15"))
    )
    (comp (ref "R6A")
      (value "1k")
      (footprint "eagle-import:RESC2012X60N")
      (fields
        (field (name "MANUFACTURER_PART_NUMBER") "CHP0805-FX-1001ELF")
        (field (name "MOUSER_PART_NUMBER") "652-CHP0805FX1001ELF")
      )
      (libsource (lib "eagle-import") (part "CHP0805-FX-1001ELF"))
    )
    (comp (ref "R6B")
      (value "1k")
      (footprint "eagle-import:RESC2012X60N")
      (fields
        (field (name "MANUFACTURER_PART_NUMBER") "CHP0805-FX-1001ELF")
        (field (name "MOUSER_PART_NUMBER") "652-CHP0805FX1001ELF")
      )
      (libsource (lib "eagle-import") (part "CHP0805-FX-1001ELF"))
    )
    (comp (ref "R6B2")
      (value "1k")
      (footprint "eagle-import:RESC2012X60N")
      (fields
        (field (name "MANUFACTURER_PART_NUMBER") "CHP0805-FX-1001ELF")
        (field (name "MOUSER_PART_NUMBER") "652-CHP0805FX1001ELF")
      )
      (libsource (lib "eagle-import") (part "CHP0805-FX-1001ELF"))
    )
    (comp (ref "R6B4")
      (value "1k")
      (footprint "eagle-import:RESC2012X60N")
      (fields
        (field (name "MANUFACTURER_PART_NUMBER") "CHP0805-FX-1001ELF")
        (field (name "MOUSER_PART_NUMBER") "652-CHP0805FX1001ELF")
      )
      (libsource (lib "eagle-import") (part "CHP0805-FX-1001ELF"))
    )
    (comp (ref "R6B6")
      (value "1k")
      (footprint "eagle-import:RESC2012X60N")
      (fields
        (field (name "MANUFACTURER_PART_NUMBER") "CHP0805-FX-1001ELF")
        (field (name "MOUSER_PART_NUMBER") "652-CHP0805FX1001ELF")
      )
      (libsource (lib "eagle-import") (part "CHP0805-FX-1001ELF"))
    )
    (comp (ref "R6D")
      (value "1k")
      (footprint "eagle-import:RESC2012X60N")
      (fields
        (field (name "MANUFACTURER_PART_NUMBER") "CHP0805-FX-1001ELF")
        (field (name "MOUSER_PART_NUMBER") "652-CHP0805FX1001ELF")
      )
      (libsource (lib "eagle-import") (part "CHP0805-FX-1001ELF"))
    )
    (comp (ref "R6P")
      (value "330")
      (footprint "eagle-import:0411_15")
      (fields
        (field (name "MANUFACTURER_PART_NUMBER") "PR02000203300JA100")
        (field (name "MOUSER_PART_NUMBER") "594-5083NW330R0JA100")
      )
      (libsource (lib "eagle-import") (part "PR02000203300JA1000411/15"))
    )
    (comp (ref "R6P1")
      (value "330")
      (footprint "eagle-import:0411_15")
      (fields
        (field (name "MANUFACTURER_PART_NUMBER") "PR02000203300JA100")
        (field (name "MOUSER_PART_NUMBER") "594-5083NW330R0JA100")
      )
      (libsource (lib "eagle-import") (part "PR02000203300JA1000411/15"))
    )
    (comp (ref "R6P2")
      (value "330")
      (footprint "eagle-import:0411_15")
      (fields
        (field (name "MANUFACTURER_PART_NUMBER") "PR02000203300JA100")
        (field (name "MOUSER_PART_NUMBER") "594-5083NW330R0JA100")
      )
      (libsource (lib "eagle-import") (part "PR02000203300JA1000411/15"))
    )
    (comp (ref "R6P3")
      (value "330")
      (footprint "eagle-import:0411_15")
      (fields
        (field (name "MANUFACTURER_PART_NUMBER") "PR02000203300JA100")
        (field (name "MOUSER_PART_NUMBER") "594-5083NW330R0JA100")
      )
      (libsource (lib "eagle-import") (part "PR02000203300JA1000411/15"))
    )
    (comp (ref "R7")
      (value "1k")
      (footprint "eagle-import:0207_10")
      (fields
        (field (name "MANUFACTURER_PART_NUMBER") "LR1F1K0")
        (field (name "MOUSER_PART_NUMBER") "279-LR1F1K0")
      )
      (libsource (lib "eagle-import") (part "LR1F1K0"))
    )
    (comp (ref "R7A")
      (value "33k")
      (footprint "eagle-import:RESC2012X65N")
      (fields
        (field (name "MANUFACTURER_PART_NUMBER") "CPF0805B33KE1")
        (field (name "MOUSER_PART_NUMBER") "279-CPF0805B33KE1")
      )
      (libsource (lib "eagle-import") (part "CPF0805B33KE1"))
    )
    (comp (ref "R7B")
      (value "33k")
      (footprint "eagle-import:R0805")
      (fields
        (field (name "MANUFACTURER_PART_NUMBER") "CPF0805B51KE1")
        (field (name "MOUSER_PART_NUMBER") "279-CPF0805B51KE1")
      )
      (libsource (lib "eagle-import") (part "CPF0805B51KE1"))
    )
    (comp (ref "R7B2")
      (value "33k")
      (footprint "eagle-import:R0805")
      (fields
        (field (name "MANUFACTURER_PART_NUMBER") "CPF0805B51KE1")
        (field (name "MOUSER_PART_NUMBER") "279-CPF0805B51KE1")
      )
      (libsource (lib "eagle-import") (part "CPF0805B51KE1"))
    )
    (comp (ref "R7B4")
      (value "33k")
      (footprint "eagle-import:R0805")
      (fields
        (field (name "MANUFACTURER_PART_NUMBER") "CPF0805B51KE1")
        (field (name "MOUSER_PART_NUMBER") "279-CPF0805B51KE1")
      )
      (libsource (lib "eagle-import") (part "CPF0805B51KE1"))
    )
    (comp (ref "R7B6")
      (value "33k")
      (footprint "eagle-import:RESC2012X65N")
      (fields
        (field (name "MANUFACTURER_PART_NUMBER") "CPF0805B33KE1")
        (field (name "MOUSER_PART_NUMBER") "279-CPF0805B33KE1")
      )
      (libsource (lib "eagle-import") (part "CPF0805B33KE1"))
    )
    (comp (ref "R7D")
      (value "33k")
      (footprint "eagle-import:R0805")
      (fields
        (field (name "MANUFACTURER_PART_NUMBER") "CPF0805B51KE1")
        (field (name "MOUSER_PART_NUMBER") "279-CPF0805B51KE1")
      )
      (libsource (lib "eagle-import") (part "CPF0805B51KE1"))
    )
    (comp (ref "R8")
      (value "1k")
      (footprint "eagle-import:0207_10")
      (fields
        (field (name "MANUFACTURER_PART_NUMBER") "LR1F1K0")
        (field (name "MOUSER_PART_NUMBER") "279-LR1F1K0")
      )
      (libsource (lib "eagle-import") (part "LR1F1K0"))
    )
    (comp (ref "R8A")
      (value "200k")
      (footprint "eagle-import:R0805")
      (fields
        (field (name "MANUFACTURER_PART_NUMBER") "RR1220P-204-D")
        (field (name "MOUSER_PART_NUMBER") "754-RR1220P-204D")
      )
      (libsource (lib "eagle-import") (part "RR1220P-204-D"))
    )
    (comp (ref "R8B")
      (value "200k")
      (footprint "eagle-import:R0805")
      (fields
        (field (name "MANUFACTURER_PART_NUMBER") "RR1220P-204-D")
        (field (name "MOUSER_PART_NUMBER") "754-RR1220P-204D")
      )
      (libsource (lib "eagle-import") (part "RR1220P-204-D"))
    )
    (comp (ref "R8B2")
      (value "200k")
      (footprint "eagle-import:R0805")
      (fields
        (field (name "MANUFACTURER_PART_NUMBER") "RR1220P-204-D")
        (field (name "MOUSER_PART_NUMBER") "754-RR1220P-204D")
      )
      (libsource (lib "eagle-import") (part "RR1220P-204-D"))
    )
    (comp (ref "R8B4")
      (value "200k")
      (footprint "eagle-import:R0805")
      (fields
        (field (name "MANUFACTURER_PART_NUMBER") "RR1220P-204-D")
        (field (name "MOUSER_PART_NUMBER") "754-RR1220P-204D")
      )
      (libsource (lib "eagle-import") (part "RR1220P-204-D"))
    )
    (comp (ref "R8B6")
      (value "200k")
      (footprint "eagle-import:R0805")
      (fields
        (field (name "MANUFACTURER_PART_NUMBER") "RR1220P-204-D")
        (field (name "MOUSER_PART_NUMBER") "754-RR1220P-204D")
      )
      (libsource (lib "eagle-import") (part "RR1220P-204-D"))
    )
    (comp (ref "R8D")
      (value "200k")
      (footprint "eagle-import:R0805")
      (fields
        (field (name "MANUFACTURER_PART_NUMBER") "RR1220P-204-D")
        (field (name "MOUSER_PART_NUMBER") "754-RR1220P-204D")
      )
      (libsource (lib "eagle-import") (part "RR1220P-204-D"))
    )
    (comp (ref "R9")
      (value "249")
      (footprint "eagle-import:0207_10")
      (fields (field (name "MANUFACTURER_PART_NUMBER") "MBB02070C2490FRP00"))
      (libsource (lib "eagle-import") (part "MBB02070C2490FRP00"))
    )
    (comp (ref "R10")
      (value "76.8")
      (footprint "eagle-import:0207_10")
      (fields (field (name "MANUFACTURER_PART_NUMBER") "YR1B76R8CC"))
      (libsource (lib "eagle-import") (part "YR1B76R8CC"))
    )
    (comp (ref "R11")
      (value "15k")
      (footprint "eagle-import:0411_15")
      (fields
        (field (name "MANUFACTURER_PART_NUMBER") "CPF215K000FKE14")
        (field (name "MOUSER_PART_NUMBER") "71-CPF2-F-15K-E3")
      )
      (libsource (lib "eagle-import") (part "CPF215K000FKE14"))
    )
    (comp (ref "R11O")
      (value "10k")
      (footprint "eagle-import:0207_10")
      (fields
        (field (name "MANUFACTURER_PART_NUMBER") "LR1F10K")
        (field (name "MOUSER_PART_NUMBER") "279-LR1F10K")
      )
      (libsource (lib "eagle-import") (part "LR1F10K"))
    )
    (comp (ref "R12O")
      (value "182")
      (footprint "eagle-import:0207_10")
      (fields
        (field (name "MANUFACTURER") "Yageo")
        (field (name "MANUFACTURER_PART_NUMBER") "MF0207FTE52-182R")
        (field (name "MOUSER_PART_NUMBER") "603-MF0207FTE52-182R")
      )
      (libsource (lib "eagle-import") (part "MF0207FTE52-182R"))
    )
    (comp (ref "R13")
      (value "1k")
      (footprint "eagle-import:0207_10")
      (fields
        (field (name "MANUFACTURER_PART_NUMBER") "LR1F1K0")
        (field (name "MOUSER_PART_NUMBER") "279-LR1F1K0")
      )
      (libsource (lib "eagle-import") (part "LR1F1K0"))
    )
    (comp (ref "R14")
      (value "1k")
      (footprint "eagle-import:0207_10")
      (fields
        (field (name "MANUFACTURER_PART_NUMBER") "LR1F1K0")
        (field (name "MOUSER_PART_NUMBER") "279-LR1F1K0")
      )
      (libsource (lib "eagle-import") (part "LR1F1K0"))
    )
    (comp (ref "R14O")
      (value "182")
      (footprint "eagle-import:0207_10")
      (fields
        (field (name "MANUFACTURER") "Yageo")
        (field (name "MANUFACTURER_PART_NUMBER") "MF0207FTE52-182R")
        (field (name "MOUSER_PART_NUMBER") "603-MF0207FTE52-182R")
      )
      (libsource (lib "eagle-import") (part "MF0207FTE52-182R"))
    )
    (comp (ref "R15")
      (value "249")
      (footprint "eagle-import:0207_10")
      (fields (field (name "MANUFACTURER_PART_NUMBER") "MBB02070C2490FRP00"))
      (libsource (lib "eagle-import") (part "MBB02070C2490FRP00"))
    )
    (comp (ref "R16")
      (value "76.8")
      (footprint "eagle-import:0207_10")
      (fields (field (name "MANUFACTURER_PART_NUMBER") "YR1B76R8CC"))
      (libsource (lib "eagle-import") (part "YR1B76R8CC"))
    )
    (comp (ref "R16O")
      (value "182")
      (footprint "eagle-import:0207_10")
      (fields
        (field (name "MANUFACTURER") "Yageo")
        (field (name "MANUFACTURER_PART_NUMBER") "MF0207FTE52-182R")
        (field (name "MOUSER_PART_NUMBER") "603-MF0207FTE52-182R")
      )
      (libsource (lib "eagle-import") (part "MF0207FTE52-182R"))
    )
    (comp (ref "R17")
      (value "402")
      (footprint "eagle-import:0617_22")
      (fields (field (name "MANUFACTURER_PART_NUMBER") "RWR80S4020FRB12"))
      (libsource (lib "eagle-import") (part "RWR80S4020FRB12"))
    )
    (comp (ref "R18")
      (value "402")
      (footprint "eagle-import:0617_22")
      (fields (field (name "MANUFACTURER_PART_NUMBER") "RWR80S4020FRB12"))
      (libsource (lib "eagle-import") (part "RWR80S4020FRB12"))
    )
    (comp (ref "R18O")
      (value "182")
      (footprint "eagle-import:0207_10")
      (fields
        (field (name "MANUFACTURER") "Yageo")
        (field (name "MANUFACTURER_PART_NUMBER") "MF0207FTE52-182R")
        (field (name "MOUSER_PART_NUMBER") "603-MF0207FTE52-182R")
      )
      (libsource (lib "eagle-import") (part "MF0207FTE52-182R"))
    )
    (comp (ref "R19")
      (value "15k")
      (footprint "eagle-import:0411_15")
      (fields
        (field (name "MANUFACTURER_PART_NUMBER") "CPF215K000FKE14")
        (field (name "MOUSER_PART_NUMBER") "71-CPF2-F-15K-E3")
      )
      (libsource (lib "eagle-import") (part "CPF215K000FKE14"))
    )
    (comp (ref "R19O")
      (value "10k")
      (footprint "eagle-import:0207_10")
      (fields
        (field (name "MANUFACTURER_PART_NUMBER") "LR1F10K")
        (field (name "MOUSER_PART_NUMBER") "279-LR1F10K")
      )
      (libsource (lib "eagle-import") (part "LR1F10K"))
    )
    (comp (ref "R20")
      (value "15k")
      (footprint "eagle-import:0411_15")
      (fields
        (field (name "MANUFACTURER_PART_NUMBER") "CPF215K000FKE14")
        (field (name "MOUSER_PART_NUMBER") "71-CPF2-F-15K-E3")
      )
      (libsource (lib "eagle-import") (part "CPF215K000FKE14"))
    )
    (comp (ref "R20O")
      (value "10k")
      (footprint "eagle-import:0207_10")
      (fields
        (field (name "MANUFACTURER_PART_NUMBER") "LR1F10K")
        (field (name "MOUSER_PART_NUMBER") "279-LR1F10K")
      )
      (libsource (lib "eagle-import") (part "LR1F10K"))
    )
    (comp (ref "R20O1")
      (value "10k")
      (footprint "eagle-import:0207_10")
      (fields
        (field (name "MANUFACTURER_PART_NUMBER") "LR1F10K")
        (field (name "MOUSER_PART_NUMBER") "279-LR1F10K")
      )
      (libsource (lib "eagle-import") (part "LR1F10K"))
    )
    (comp (ref "R20O2")
      (value "10k")
      (footprint "eagle-import:0207_10")
      (fields
        (field (name "MANUFACTURER_PART_NUMBER") "LR1F10K")
        (field (name "MOUSER_PART_NUMBER") "279-LR1F10K")
      )
      (libsource (lib "eagle-import") (part "LR1F10K"))
    )
    (comp (ref "R21O")
      (value "10k")
      (footprint "eagle-import:0207_10")
      (fields
        (field (name "MANUFACTURER_PART_NUMBER") "LR1F10K")
        (field (name "MOUSER_PART_NUMBER") "279-LR1F10K")
      )
      (libsource (lib "eagle-import") (part "LR1F10K"))
    )
    (comp (ref "R22O")
      (value "10k")
      (footprint "eagle-import:0207_10")
      (fields
        (field (name "MANUFACTURER_PART_NUMBER") "LR1F10K")
        (field (name "MOUSER_PART_NUMBER") "279-LR1F10K")
      )
      (libsource (lib "eagle-import") (part "LR1F10K"))
    )
    (comp (ref "R23O")
      (value "182")
      (footprint "eagle-import:0207_10")
      (fields
        (field (name "MANUFACTURER") "Yageo")
        (field (name "MANUFACTURER_PART_NUMBER") "MF0207FTE52-182R")
        (field (name "MOUSER_PART_NUMBER") "603-MF0207FTE52-182R")
      )
      (libsource (lib "eagle-import") (part "MF0207FTE52-182R"))
    )
    (comp (ref "R24O")
      (value "182")
      (footprint "eagle-import:0207_10")
      (fields
        (field (name "MANUFACTURER") "Yageo")
        (field (name "MANUFACTURER_PART_NUMBER") "MF0207FTE52-182R")
        (field (name "MOUSER_PART_NUMBER") "603-MF0207FTE52-182R")
      )
      (libsource (lib "eagle-import") (part "MF0207FTE52-182R"))
    )
    (comp (ref "R25O")
      (value "182")
      (footprint "eagle-import:0207_10")
      (fields
        (field (name "MANUFACTURER") "Yageo")
        (field (name "MANUFACTURER_PART_NUMBER") "MF0207FTE52-182R")
        (field (name "MOUSER_PART_NUMBER") "603-MF0207FTE52-182R")
      )
      (libsource (lib "eagle-import") (part "MF0207FTE52-182R"))
    )
    (comp (ref "R26O")
      (value "182")
      (footprint "eagle-import:0207_10")
      (fields
        (field (name "MANUFACTURER") "Yageo")
        (field (name "MANUFACTURER_PART_NUMBER") "MF0207FTE52-182R")
        (field (name "MOUSER_PART_NUMBER") "603-MF0207FTE52-182R")
      )
      (libsource (lib "eagle-import") (part "MF0207FTE52-182R"))
    )
    (comp (ref "R28O")
      (value "10k")
      (footprint "eagle-import:0207_10")
      (fields
        (field (name "MANUFACTURER_PART_NUMBER") "LR1F10K")
        (field (name "MOUSER_PART_NUMBER") "279-LR1F10K")
      )
      (libsource (lib "eagle-import") (part "LR1F10K"))
    )
    (comp (ref "R29O")
      (value "10k")
      (footprint "eagle-import:0207_10")
      (fields
        (field (name "MANUFACTURER_PART_NUMBER") "LR1F10K")
        (field (name "MOUSER_PART_NUMBER") "279-LR1F10K")
      )
      (libsource (lib "eagle-import") (part "LR1F10K"))
    )
    (comp (ref "R30O")
      (value "10k")
      (footprint "eagle-import:0207_10")
      (fields
        (field (name "MANUFACTURER_PART_NUMBER") "LR1F10K")
        (field (name "MOUSER_PART_NUMBER") "279-LR1F10K")
      )
      (libsource (lib "eagle-import") (part "LR1F10K"))
    )
    (comp (ref "SX1")
      (value "VT9-PT")
      (footprint "eagle-import:VT9-PT")
      (libsource (lib "eagle-import") (part "VT9-PT"))
    )
    (comp (ref "SX2")
      (value "VT9-PT")
      (footprint "eagle-import:VT9-PT")
      (libsource (lib "eagle-import") (part "VT9-PT"))
    )
    (comp (ref "SX3")
      (value "VT9-PT")
      (footprint "eagle-import:VT9-PT")
      (libsource (lib "eagle-import") (part "VT9-PT"))
    )
    (comp (ref "SX4")
      (value "VT9-PT")
      (footprint "eagle-import:VT9-PT")
      (libsource (lib "eagle-import") (part "VT9-PT"))
    )
    (comp (ref "U1")
      (value "LM317MTG")
      (footprint "eagle-import:TO254P482X997X2018-3P")
      (fields (field (name "MOUSER_PART_NUMBER") "863-LM317MTG"))
      (libsource (lib "eagle-import") (part "LM317MTG"))
    )
    (comp (ref "U2")
      (value "LM317MTG")
      (footprint "eagle-import:TO254P482X997X2018-3P")
      (fields (field (name "MOUSER_PART_NUMBER") "863-LM317MTG"))
      (libsource (lib "eagle-import") (part "LM317MTG"))
    )
    (comp (ref "Z1")
      (value "BZX79-C16,113")
      (footprint "eagle-import:DIOAD1165W56L425D185")
      (libsource (lib "eagle-import") (part "BZX79-C16,113"))
    )
    (comp (ref "Z2")
      (value "BZX79-C16,113")
      (footprint "eagle-import:DIOAD1165W56L425D185")
      (libsource (lib "eagle-import") (part "BZX79-C16,113"))
    )
    (comp (ref "Z3")
      (value "1N750")
      (footprint "eagle-import:DIOAD1256W56L444D203")
      (fields (field (name "MOUSER_PART_NUMBER") "494-1N750(DO-35)"))
      (libsource (lib "eagle-import") (part "1N750"))
    )
    (comp (ref "Z4")
      (value "1N750")
      (footprint "eagle-import:DIOAD1256W56L444D203")
      (fields (field (name "MOUSER_PART_NUMBER") "494-1N750(DO-35)"))
      (libsource (lib "eagle-import") (part "1N750"))
    )
    (comp (ref "Z5")
      (value "BZX79-C16,113")
      (footprint "eagle-import:DIOAD1165W56L425D185")
      (libsource (lib "eagle-import") (part "BZX79-C16,113"))
    )
    (comp (ref "Z6")
      (value "BZX79-C16,113")
      (footprint "eagle-import:DIOAD1165W56L425D185")
      (libsource (lib "eagle-import") (part "BZX79-C16,113"))
    )
  )
  (nets
    (net (code "1") (name "+1V8{slash}1") (class "Default")
      (node (ref "C27A1") (pin "1") (pinfunction "1_1") (pintype "passive"))
      (node (ref "C28A1") (pin "1") (pinfunction "1_1") (pintype "passive"))
      (node (ref "J9") (pin "6") (pinfunction "6_6") (pintype "bidirectional"))
      (node (ref "LDO1") (pin "5") (pinfunction "VOUT_5") (pintype "bidirectional"))
    )
    (net (code "2") (name "+1V8{slash}2") (class "Default")
      (node (ref "C27A") (pin "1") (pinfunction "1_1") (pintype "passive"))
      (node (ref "C28A") (pin "1") (pinfunction "1_1") (pintype "passive"))
      (node (ref "J7") (pin "1") (pinfunction "1_1") (pintype "bidirectional"))
      (node (ref "LDO7") (pin "5") (pinfunction "VOUT_5") (pintype "bidirectional"))
    )
    (net (code "3") (name "+3V3{slash}1") (class "Default")
      (node (ref "C18B6") (pin "1") (pinfunction "1_1") (pintype "passive"))
      (node (ref "C26A1") (pin "1") (pinfunction "1_1") (pintype "passive"))
      (node (ref "IC10") (pin "10") (pinfunction "OUT_10") (pintype "bidirectional"))
      (node (ref "IC10") (pin "9") (pinfunction "OUTS_9") (pintype "bidirectional"))
      (node (ref "J12") (pin "6") (pinfunction "6_6") (pintype "bidirectional"))
      (node (ref "J9") (pin "4") (pinfunction "4_4") (pintype "bidirectional"))
      (node (ref "LDO1") (pin "1") (pinfunction "VIN_1") (pintype "bidirectional"))
      (node (ref "LDO1") (pin "3") (pinfunction "EN_3") (pintype "bidirectional"))
    )
    (net (code "4") (name "+3V3{slash}2") (class "Default")
      (node (ref "C18A") (pin "1") (pinfunction "1_1") (pintype "passive"))
      (node (ref "C26A") (pin "1") (pinfunction "1_1") (pintype "passive"))
      (node (ref "IC2") (pin "10") (pinfunction "OUT_10") (pintype "bidirectional"))
      (node (ref "IC2") (pin "9") (pinfunction "OUTS_9") (pintype "bidirectional"))
      (node (ref "J5") (pin "6") (pinfunction "6_6") (pintype "bidirectional"))
      (node (ref "J7") (pin "3") (pinfunction "3_3") (pintype "bidirectional"))
      (node (ref "LDO7") (pin "1") (pinfunction "VIN_1") (pintype "bidirectional"))
      (node (ref "LDO7") (pin "3") (pinfunction "EN_3") (pintype "bidirectional"))
    )
    (net (code "5") (name "+5V{slash}L{slash}1") (class "Default")
      (node (ref "C18D") (pin "1") (pinfunction "1_1") (pintype "passive"))
      (node (ref "IC1") (pin "10") (pinfunction "OUT_10") (pintype "bidirectional"))
      (node (ref "IC1") (pin "9") (pinfunction "OUTS_9") (pintype "bidirectional"))
      (node (ref "J1") (pin "6") (pinfunction "6_6") (pintype "bidirectional"))
      (node (ref "J7") (pin "4") (pinfunction "4_4") (pintype "bidirectional"))
    )
    (net (code "6") (name "+5V{slash}L{slash}2") (class "Default")
      (node (ref "C18B") (pin "1") (pinfunction "1_1") (pintype "passive"))
      (node (ref "IC5") (pin "10") (pinfunction "OUT_10") (pintype "bidirectional"))
      (node (ref "IC5") (pin "9") (pinfunction "OUTS_9") (pintype "bidirectional"))
      (node (ref "J17") (pin "6") (pinfunction "6_6") (pintype "bidirectional"))
      (node (ref "J7") (pin "5") (pinfunction "5_5") (pintype "bidirectional"))
    )
    (net (code "7") (name "+5V{slash}L{slash}3") (class "Default")
      (node (ref "C20A") (pin "1") (pinfunction "1_1") (pintype "passive"))
      (node (ref "C21A") (pin "1") (pinfunction "1_1") (pintype "passive"))
      (node (ref "C8") (pin "1") (pinfunction "+_1") (pintype "bidirectional"))
      (node (ref "IC2") (pin "1") (pinfunction "IN_1") (pintype "bidirectional"))
      (node (ref "IC2") (pin "2") (pinfunction "IN_2") (pintype "bidirectional"))
      (node (ref "IC2") (pin "3") (pinfunction "EN/UV_3") (pintype "bidirectional"))
      (node (ref "IC3") (pin "2") (pinfunction "OUT_2") (pintype "passive"))
      (node (ref "IC3") (pin "4") (pinfunction "OUT_4") (pintype "passive"))
      (node (ref "J5") (pin "7") (pinfunction "7_7") (pintype "bidirectional"))
      (node (ref "J5") (pin "8") (pinfunction "8_8") (pintype "bidirectional"))
      (node (ref "J7") (pin "2") (pinfunction "2_2") (pintype "bidirectional"))
      (node (ref "R8A") (pin "1") (pinfunction "1_1") (pintype "passive"))
    )
    (net (code "8") (name "+5V{slash}R{slash}1") (class "Default")
      (node (ref "C18B4") (pin "1") (pinfunction "1_1") (pintype "passive"))
      (node (ref "IC8") (pin "10") (pinfunction "OUT_10") (pintype "bidirectional"))
      (node (ref "IC8") (pin "9") (pinfunction "OUTS_9") (pintype "bidirectional"))
      (node (ref "J10") (pin "6") (pinfunction "6_6") (pintype "bidirectional"))
      (node (ref "J9") (pin "3") (pinfunction "3_3") (pintype "bidirectional"))
    )
    (net (code "9") (name "+5V{slash}R{slash}2") (class "Default")
      (node (ref "C18B2") (pin "1") (pinfunction "1_1") (pintype "passive"))
      (node (ref "IC6") (pin "10") (pinfunction "OUT_10") (pintype "bidirectional"))
      (node (ref "IC6") (pin "9") (pinfunction "OUTS_9") (pintype "bidirectional"))
      (node (ref "J8") (pin "6") (pinfunction "6_6") (pintype "bidirectional"))
      (node (ref "J9") (pin "2") (pinfunction "2_2") (pintype "bidirectional"))
    )
    (net (code "10") (name "+5V{slash}R{slash}3") (class "Default")
      (node (ref "C5") (pin "1") (pinfunction "+_1") (pintype "bidirectional"))
      (node (ref "IC4") (pin "2") (pinfunction "OUT_2") (pintype "passive"))
      (node (ref "IC4") (pin "4") (pinfunction "OUT_4") (pintype "passive"))
      (node (ref "J9") (pin "5") (pinfunction "5_5") (pintype "bidirectional"))
    )
    (net (code "11") (name "+240VDC{slash}1") (class "Default")
      (node (ref "C1") (pin "1") (pinfunction "1_1") (pintype "passive"))
      (node (ref "C3") (pin "1") (pinfunction "1_1") (pintype "passive"))
      (node (ref "C3P2") (pin "1") (pinfunction "+_1") (pintype "bidirectional"))
      (node (ref "C5P2") (pin "1") (pinfunction "+_1") (pintype "bidirectional"))
      (node (ref "C6P2") (pin "1") (pinfunction "+_1") (pintype "bidirectional"))
      (node (ref "C7P2") (pin "1") (pinfunction "+_1") (pintype "bidirectional"))
      (node (ref "R17") (pin "1") (pinfunction "1_1") (pintype "passive"))
      (node (ref "R19") (pin "2") (pinfunction "2_2") (pintype "passive"))
      (node (ref "R4P1") (pin "2") (pinfunction "2_2") (pintype "passive"))
      (node (ref "R5") (pin "2") (pinfunction "2_2") (pintype "passive"))
      (node (ref "R6P2") (pin "1") (pinfunction "1_1") (pintype "passive"))
    )
    (net (code "12") (name "+240VDC{slash}2") (class "Default")
      (node (ref "C2") (pin "1") (pinfunction "1_1") (pintype "passive"))
      (node (ref "C3P") (pin "1") (pinfunction "+_1") (pintype "bidirectional"))
      (node (ref "C4") (pin "1") (pinfunction "1_1") (pintype "passive"))
      (node (ref "C5P") (pin "1") (pinfunction "+_1") (pintype "bidirectional"))
      (node (ref "C6P") (pin "1") (pinfunction "+_1") (pintype "bidirectional"))
      (node (ref "C7P") (pin "1") (pinfunction "+_1") (pintype "bidirectional"))
      (node (ref "R11") (pin "2") (pinfunction "2_2") (pintype "passive"))
      (node (ref "R18") (pin "2") (pinfunction "2_2") (pintype "passive"))
      (node (ref "R20") (pin "1") (pinfunction "1_1") (pintype "passive"))
      (node (ref "R4P") (pin "2") (pinfunction "2_2") (pintype "passive"))
      (node (ref "R6P") (pin "1") (pinfunction "1_1") (pintype "passive"))
    )
    (net (code "13") (name "6.3_VAC_BLU{slash}1") (class "Default")
      (node (ref "D19") (pin "1") (pinfunction "K_1") (pintype "bidirectional"))
      (node (ref "D22") (pin "2") (pinfunction "A_2") (pintype "bidirectional"))
      (node (ref "J4") (pin "4") (pinfunction "4_4") (pintype "bidirectional"))
    )
    (net (code "14") (name "6.3_VAC_BLU{slash}2") (class "Default")
      (node (ref "D11") (pin "1") (pinfunction "K_1") (pintype "bidirectional"))
      (node (ref "D14") (pin "2") (pinfunction "A_2") (pintype "bidirectional"))
      (node (ref "J6") (pin "8") (pinfunction "8_8") (pintype "bidirectional"))
    )
    (net (code "15") (name "6.3_VAC_GRN{slash}1") (class "Default")
      (node (ref "D20") (pin "1") (pinfunction "K_1") (pintype "bidirectional"))
      (node (ref "D21") (pin "2") (pinfunction "A_2") (pintype "bidirectional"))
      (node (ref "J4") (pin "3") (pinfunction "3_3") (pintype "bidirectional"))
    )
    (net (code "16") (name "6.3_VAC_GRN{slash}2") (class "Default")
      (node (ref "D12") (pin "1") (pinfunction "K_1") (pintype "bidirectional"))
      (node (ref "D13") (pin "2") (pinfunction "A_2") (pintype "bidirectional"))
      (node (ref "J6") (pin "9") (pinfunction "9_9") (pintype "bidirectional"))
    )
    (net (code "17") (name "66.3VAC{slash}BRN{slash}1") (class "Default")
      (node (ref "J4") (pin "5") (pinfunction "5_5") (pintype "bidirectional"))
      (node (ref "R3P1") (pin "1") (pinfunction "1_1") (pintype "passive"))
      (node (ref "SX1") (pin "4") (pinfunction "4_4") (pintype "passive"))
      (node (ref "SX3") (pin "4") (pinfunction "4_4") (pintype "passive"))
    )
    (net (code "18") (name "66.3VAC{slash}BRN{slash}2") (class "Default")
      (node (ref "J6") (pin "7") (pinfunction "7_7") (pintype "bidirectional"))
      (node (ref "R3P") (pin "1") (pinfunction "1_1") (pintype "passive"))
      (node (ref "SX2") (pin "4") (pinfunction "4_4") (pintype "passive"))
      (node (ref "SX4") (pin "4") (pinfunction "4_4") (pintype "passive"))
    )
    (net (code "19") (name "66.3VAC{slash}ORG{slash}1") (class "Default")
      (node (ref "J4") (pin "6") (pinfunction "6_6") (pintype "bidirectional"))
      (node (ref "R2P1") (pin "2") (pinfunction "2_2") (pintype "passive"))
      (node (ref "SX1") (pin "5") (pinfunction "5_5") (pintype "passive"))
      (node (ref "SX3") (pin "5") (pinfunction "5_5") (pintype "passive"))
    )
    (net (code "20") (name "66.3VAC{slash}ORG{slash}2") (class "Default")
      (node (ref "J6") (pin "6") (pinfunction "6_6") (pintype "bidirectional"))
      (node (ref "R2P") (pin "2") (pinfunction "2_2") (pintype "passive"))
      (node (ref "SX2") (pin "5") (pinfunction "5_5") (pintype "passive"))
      (node (ref "SX4") (pin "5") (pinfunction "5_5") (pintype "passive"))
    )
    (net (code "21") (name "115_VAC_BLK{slash}1") (class "Default")
      (node (ref "D15") (pin "1") (pinfunction "K_1") (pintype "bidirectional"))
      (node (ref "D18") (pin "2") (pinfunction "A_2") (pintype "bidirectional"))
      (node (ref "J4") (pin "10") (pinfunction "10_10") (pintype "bidirectional"))
    )
    (net (code "22") (name "115_VAC_BLK{slash}2") (class "Default")
      (node (ref "D10") (pin "2") (pinfunction "A_2") (pintype "bidirectional"))
      (node (ref "D7") (pin "1") (pinfunction "K_1") (pintype "bidirectional"))
      (node (ref "J6") (pin "2") (pinfunction "2_2") (pintype "bidirectional"))
    )
    (net (code "23") (name "115_VAC_RED{slash}1") (class "Default")
      (node (ref "D16") (pin "1") (pinfunction "K_1") (pintype "bidirectional"))
      (node (ref "D17") (pin "2") (pinfunction "A_2") (pintype "bidirectional"))
      (node (ref "J4") (pin "9") (pinfunction "9_9") (pintype "bidirectional"))
    )
    (net (code "24") (name "115_VAC_RED{slash}2") (class "Default")
      (node (ref "D8") (pin "1") (pinfunction "K_1") (pintype "bidirectional"))
      (node (ref "D9") (pin "2") (pinfunction "A_2") (pintype "bidirectional"))
      (node (ref "J6") (pin "3") (pinfunction "3_3") (pintype "bidirectional"))
    )
    (net (code "25") (name "AGND{slash}1") (class "Default")
      (node (ref "C1") (pin "2") (pinfunction "2_2") (pintype "passive"))
      (node (ref "C1P2") (pin "2") (pinfunction "-_2") (pintype "bidirectional"))
      (node (ref "C2P2") (pin "2") (pinfunction "-_2") (pintype "bidirectional"))
      (node (ref "C3") (pin "2") (pinfunction "2_2") (pintype "passive"))
      (node (ref "C3P2") (pin "2") (pinfunction "-_2") (pintype "bidirectional"))
      (node (ref "C4P1") (pin "2") (pinfunction "-_2") (pintype "bidirectional"))
      (node (ref "C5P2") (pin "2") (pinfunction "-_2") (pintype "bidirectional"))
      (node (ref "C6P2") (pin "2") (pinfunction "-_2") (pintype "bidirectional"))
      (node (ref "C7P2") (pin "2") (pinfunction "-_2") (pintype "bidirectional"))
      (node (ref "D15") (pin "2") (pinfunction "A_2") (pintype "bidirectional"))
      (node (ref "D16") (pin "2") (pinfunction "A_2") (pintype "bidirectional"))
      (node (ref "J13") (pin "2") (pinfunction "2_2") (pintype "passive"))
      (node (ref "J13") (pin "5") (pinfunction "5_5") (pintype "passive"))
      (node (ref "J3") (pin "1") (pinfunction "SLEEVE_1") (pintype "bidirectional"))
      (node (ref "R10") (pin "1") (pinfunction "1_1") (pintype "passive"))
      (node (ref "R11O") (pin "2") (pinfunction "2_2") (pintype "passive"))
      (node (ref "R19O") (pin "1") (pinfunction "1_1") (pintype "passive"))
      (node (ref "R20O") (pin "2") (pinfunction "2_2") (pintype "passive"))
      (node (ref "R20O1") (pin "1") (pinfunction "1_1") (pintype "passive"))
      (node (ref "R21O") (pin "1") (pinfunction "1_1") (pintype "passive"))
      (node (ref "R3O") (pin "2") (pinfunction "2_2") (pintype "passive"))
      (node (ref "R5P1") (pin "1") (pinfunction "1_1") (pintype "passive"))
      (node (ref "R9") (pin "1") (pinfunction "1_1") (pintype "passive"))
      (node (ref "U1") (pin "1") (pinfunction "ADJ_1") (pintype "input"))
      (node (ref "Z1") (pin "1") (pinfunction "C_1") (pintype "passive"))
    )
    (net (code "26") (name "AGND{slash}2") (class "Default")
      (node (ref "C1P") (pin "2") (pinfunction "-_2") (pintype "bidirectional"))
      (node (ref "C2") (pin "2") (pinfunction "2_2") (pintype "passive"))
      (node (ref "C2P") (pin "2") (pinfunction "-_2") (pintype "bidirectional"))
      (node (ref "C3P") (pin "2") (pinfunction "-_2") (pintype "bidirectional"))
      (node (ref "C4") (pin "2") (pinfunction "2_2") (pintype "passive"))
      (node (ref "C4P") (pin "2") (pinfunction "-_2") (pintype "bidirectional"))
      (node (ref "C5P") (pin "2") (pinfunction "-_2") (pintype "bidirectional"))
      (node (ref "C6P") (pin "2") (pinfunction "-_2") (pintype "bidirectional"))
      (node (ref "C7P") (pin "2") (pinfunction "-_2") (pintype "bidirectional"))
      (node (ref "D7") (pin "2") (pinfunction "A_2") (pintype "bidirectional"))
      (node (ref "D8") (pin "2") (pinfunction "A_2") (pintype "bidirectional"))
      (node (ref "J2") (pin "2") (pinfunction "2_2") (pintype "passive"))
      (node (ref "J2") (pin "5") (pinfunction "5_5") (pintype "passive"))
      (node (ref "R15") (pin "1") (pinfunction "1_1") (pintype "passive"))
      (node (ref "R16") (pin "1") (pinfunction "1_1") (pintype "passive"))
      (node (ref "R20O2") (pin "1") (pinfunction "1_1") (pintype "passive"))
      (node (ref "R22O") (pin "2") (pinfunction "2_2") (pintype "passive"))
      (node (ref "R28O") (pin "1") (pinfunction "1_1") (pintype "passive"))
      (node (ref "R29O") (pin "2") (pinfunction "2_2") (pintype "passive"))
      (node (ref "R30O") (pin "1") (pinfunction "1_1") (pintype "passive"))
      (node (ref "R3O1") (pin "2") (pinfunction "2_2") (pintype "passive"))
      (node (ref "R5P") (pin "1") (pinfunction "1_1") (pintype "passive"))
      (node (ref "U2") (pin "1") (pinfunction "ADJ_1") (pintype "input"))
      (node (ref "Z6") (pin "1") (pinfunction "C_1") (pintype "passive"))
    )
    (net (code "27") (name "DGND{slash}1") (class "Default")
      (node (ref "C18B2") (pin "2") (pinfunction "2_2") (pintype "passive"))
      (node (ref "C18B4") (pin "2") (pinfunction "2_2") (pintype "passive"))
      (node (ref "C18B6") (pin "2") (pinfunction "2_2") (pintype "passive"))
      (node (ref "C19B2") (pin "2") (pinfunction "2_2") (pintype "passive"))
      (node (ref "C19B2") (pin "DGND") (pinfunction "2_DGND") (pintype "passive"))
      (node (ref "C19B4") (pin "2") (pinfunction "2_2") (pintype "passive"))
      (node (ref "C19B4") (pin "DGND") (pinfunction "2_DGND") (pintype "passive"))
      (node (ref "C19B6") (pin "2") (pinfunction "2_2") (pintype "passive"))
      (node (ref "C19B6") (pin "DGND") (pinfunction "2_DGND") (pintype "passive"))
      (node (ref "C1P3") (pin "2") (pinfunction "-_2") (pintype "bidirectional"))
      (node (ref "C20B2") (pin "2") (pinfunction "2_2") (pintype "passive"))
      (node (ref "C20B4") (pin "2") (pinfunction "2_2") (pintype "passive"))
      (node (ref "C20B6") (pin "2") (pinfunction "2_2") (pintype "passive"))
      (node (ref "C21B2") (pin "2") (pinfunction "2_2") (pintype "passive"))
      (node (ref "C21B4") (pin "2") (pinfunction "2_2") (pintype "passive"))
      (node (ref "C21B6") (pin "2") (pinfunction "2_2") (pintype "passive"))
      (node (ref "C26A1") (pin "2") (pinfunction "2_2") (pintype "passive"))
      (node (ref "C27A1") (pin "2") (pinfunction "2_2") (pintype "passive"))
      (node (ref "C28A1") (pin "2") (pinfunction "2_2") (pintype "passive"))
      (node (ref "C2P3") (pin "2") (pinfunction "-_2") (pintype "bidirectional"))
      (node (ref "C3P3") (pin "2") (pinfunction "-_2") (pintype "bidirectional"))
      (node (ref "C5") (pin "2") (pinfunction "-_2") (pintype "bidirectional"))
      (node (ref "C5P3") (pin "2") (pinfunction "-_2") (pintype "bidirectional"))
      (node (ref "C6") (pin "2") (pinfunction "-_2") (pintype "bidirectional"))
      (node (ref "C6P3") (pin "2") (pinfunction "-_2") (pintype "bidirectional"))
      (node (ref "C7P3") (pin "2") (pinfunction "-_2") (pintype "bidirectional"))
      (node (ref "D19") (pin "2") (pinfunction "A_2") (pintype "bidirectional"))
      (node (ref "D20") (pin "2") (pinfunction "A_2") (pintype "bidirectional"))
      (node (ref "IC10") (pin "11") (pinfunction "GND_11") (pintype "bidirectional"))
      (node (ref "IC10") (pin "8") (pinfunction "GND_8") (pintype "bidirectional"))
      (node (ref "IC10") (pin "P$1") (pinfunction "GND_P$1") (pintype "bidirectional"))
      (node (ref "IC10") (pin "P$2") (pinfunction "GND_P$2") (pintype "bidirectional"))
      (node (ref "IC10") (pin "P$3") (pinfunction "GND_P$3") (pintype "bidirectional"))
      (node (ref "IC10") (pin "P$4") (pinfunction "GND_P$4") (pintype "bidirectional"))
      (node (ref "IC10") (pin "P$5") (pinfunction "GND_P$5") (pintype "bidirectional"))
      (node (ref "IC10") (pin "P$6") (pinfunction "GND_P$6") (pintype "bidirectional"))
      (node (ref "IC4") (pin "1") (pinfunction "GND_1") (pintype "input"))
      (node (ref "IC6") (pin "11") (pinfunction "GND_11") (pintype "bidirectional"))
      (node (ref "IC6") (pin "8") (pinfunction "GND_8") (pintype "bidirectional"))
      (node (ref "IC6") (pin "P$1") (pinfunction "GND_P$1") (pintype "bidirectional"))
      (node (ref "IC6") (pin "P$2") (pinfunction "GND_P$2") (pintype "bidirectional"))
      (node (ref "IC6") (pin "P$3") (pinfunction "GND_P$3") (pintype "bidirectional"))
      (node (ref "IC6") (pin "P$4") (pinfunction "GND_P$4") (pintype "bidirectional"))
      (node (ref "IC6") (pin "P$5") (pinfunction "GND_P$5") (pintype "bidirectional"))
      (node (ref "IC6") (pin "P$6") (pinfunction "GND_P$6") (pintype "bidirectional"))
      (node (ref "IC8") (pin "11") (pinfunction "GND_11") (pintype "bidirectional"))
      (node (ref "IC8") (pin "8") (pinfunction "GND_8") (pintype "bidirectional"))
      (node (ref "IC8") (pin "P$1") (pinfunction "GND_P$1") (pintype "bidirectional"))
      (node (ref "IC8") (pin "P$2") (pinfunction "GND_P$2") (pintype "bidirectional"))
      (node (ref "IC8") (pin "P$3") (pinfunction "GND_P$3") (pintype "bidirectional"))
      (node (ref "IC8") (pin "P$4") (pinfunction "GND_P$4") (pintype "bidirectional"))
      (node (ref "IC8") (pin "P$5") (pinfunction "GND_P$5") (pintype "bidirectional"))
      (node (ref "IC8") (pin "P$6") (pinfunction "GND_P$6") (pintype "bidirectional"))
      (node (ref "J10") (pin "5") (pinfunction "5_5") (pintype "bidirectional"))
      (node (ref "J12") (pin "5") (pinfunction "5_5") (pintype "bidirectional"))
      (node (ref "J8") (pin "5") (pinfunction "5_5") (pintype "bidirectional"))
      (node (ref "J9") (pin "1") (pinfunction "1_1") (pintype "bidirectional"))
      (node (ref "LDO1") (pin "2") (pinfunction "GND_2") (pintype "bidirectional"))
      (node (ref "LDO1") (pin "DGND") (pinfunction "GND_DGND") (pintype "bidirectional"))
      (node (ref "LDO1") (pin "DGND2") (pinfunction "GND_DGND2") (pintype "bidirectional"))
      (node (ref "LDO1") (pin "DGND3") (pinfunction "GND_DGND3") (pintype "bidirectional"))
      (node (ref "R6B2") (pin "2") (pinfunction "2_2") (pintype "passive"))
      (node (ref "R6B4") (pin "2") (pinfunction "2_2") (pintype "passive"))
      (node (ref "R6B6") (pin "2") (pinfunction "2_2") (pintype "passive"))
      (node (ref "R7B2") (pin "2") (pinfunction "2_2") (pintype "passive"))
      (node (ref "R7B4") (pin "2") (pinfunction "2_2") (pintype "passive"))
      (node (ref "R7B6") (pin "2") (pinfunction "2_2") (pintype "passive"))
    )
    (net (code "28") (name "DGND{slash}2") (class "Default")
      (node (ref "C18A") (pin "2") (pinfunction "2_2") (pintype "passive"))
      (node (ref "C18B") (pin "2") (pinfunction "2_2") (pintype "passive"))
      (node (ref "C18D") (pin "2") (pinfunction "2_2") (pintype "passive"))
      (node (ref "C19A") (pin "2") (pinfunction "2_2") (pintype "passive"))
      (node (ref "C19A") (pin "DGND") (pinfunction "2_DGND") (pintype "passive"))
      (node (ref "C19B") (pin "2") (pinfunction "2_2") (pintype "passive"))
      (node (ref "C19B") (pin "DGND") (pinfunction "2_DGND") (pintype "passive"))
      (node (ref "C19D") (pin "2") (pinfunction "2_2") (pintype "passive"))
      (node (ref "C19D") (pin "DGND") (pinfunction "2_DGND") (pintype "passive"))
      (node (ref "C1P1") (pin "2") (pinfunction "-_2") (pintype "bidirectional"))
      (node (ref "C20A") (pin "2") (pinfunction "2_2") (pintype "passive"))
      (node (ref "C20B") (pin "2") (pinfunction "2_2") (pintype "passive"))
      (node (ref "C20D") (pin "2") (pinfunction "2_2") (pintype "passive"))
      (node (ref "C21A") (pin "2") (pinfunction "2_2") (pintype "passive"))
      (node (ref "C21B") (pin "2") (pinfunction "2_2") (pintype "passive"))
      (node (ref "C21D") (pin "2") (pinfunction "2_2") (pintype "passive"))
      (node (ref "C26A") (pin "2") (pinfunction "2_2") (pintype "passive"))
      (node (ref "C27A") (pin "2") (pinfunction "2_2") (pintype "passive"))
      (node (ref "C28A") (pin "2") (pinfunction "2_2") (pintype "passive"))
      (node (ref "C2P1") (pin "2") (pinfunction "-_2") (pintype "bidirectional"))
      (node (ref "C3P1") (pin "2") (pinfunction "-_2") (pintype "bidirectional"))
      (node (ref "C5P1") (pin "2") (pinfunction "-_2") (pintype "bidirectional"))
      (node (ref "C6P1") (pin "2") (pinfunction "-_2") (pintype "bidirectional"))
      (node (ref "C7") (pin "2") (pinfunction "-_2") (pintype "bidirectional"))
      (node (ref "C7P1") (pin "2") (pinfunction "-_2") (pintype "bidirectional"))
      (node (ref "C8") (pin "2") (pinfunction "-_2") (pintype "bidirectional"))
      (node (ref "D11") (pin "2") (pinfunction "A_2") (pintype "bidirectional"))
      (node (ref "D12") (pin "2") (pinfunction "A_2") (pintype "bidirectional"))
      (node (ref "IC1") (pin "11") (pinfunction "GND_11") (pintype "bidirectional"))
      (node (ref "IC1") (pin "8") (pinfunction "GND_8") (pintype "bidirectional"))
      (node (ref "IC1") (pin "P$1") (pinfunction "GND_P$1") (pintype "bidirectional"))
      (node (ref "IC1") (pin "P$2") (pinfunction "GND_P$2") (pintype "bidirectional"))
      (node (ref "IC1") (pin "P$3") (pinfunction "GND_P$3") (pintype "bidirectional"))
      (node (ref "IC1") (pin "P$4") (pinfunction "GND_P$4") (pintype "bidirectional"))
      (node (ref "IC1") (pin "P$5") (pinfunction "GND_P$5") (pintype "bidirectional"))
      (node (ref "IC1") (pin "P$6") (pinfunction "GND_P$6") (pintype "bidirectional"))
      (node (ref "IC2") (pin "11") (pinfunction "GND_11") (pintype "bidirectional"))
      (node (ref "IC2") (pin "8") (pinfunction "GND_8") (pintype "bidirectional"))
      (node (ref "IC2") (pin "P$1") (pinfunction "GND_P$1") (pintype "bidirectional"))
      (node (ref "IC2") (pin "P$2") (pinfunction "GND_P$2") (pintype "bidirectional"))
      (node (ref "IC2") (pin "P$3") (pinfunction "GND_P$3") (pintype "bidirectional"))
      (node (ref "IC2") (pin "P$4") (pinfunction "GND_P$4") (pintype "bidirectional"))
      (node (ref "IC2") (pin "P$5") (pinfunction "GND_P$5") (pintype "bidirectional"))
      (node (ref "IC2") (pin "P$6") (pinfunction "GND_P$6") (pintype "bidirectional"))
      (node (ref "IC3") (pin "1") (pinfunction "GND_1") (pintype "input"))
      (node (ref "IC5") (pin "11") (pinfunction "GND_11") (pintype "bidirectional"))
      (node (ref "IC5") (pin "8") (pinfunction "GND_8") (pintype "bidirectional"))
      (node (ref "IC5") (pin "P$1") (pinfunction "GND_P$1") (pintype "bidirectional"))
      (node (ref "IC5") (pin "P$2") (pinfunction "GND_P$2") (pintype "bidirectional"))
      (node (ref "IC5") (pin "P$3") (pinfunction "GND_P$3") (pintype "bidirectional"))
      (node (ref "IC5") (pin "P$4") (pinfunction "GND_P$4") (pintype "bidirectional"))
      (node (ref "IC5") (pin "P$5") (pinfunction "GND_P$5") (pintype "bidirectional"))
      (node (ref "IC5") (pin "P$6") (pinfunction "GND_P$6") (pintype "bidirectional"))
      (node (ref "J1") (pin "5") (pinfunction "5_5") (pintype "bidirectional"))
      (node (ref "J17") (pin "5") (pinfunction "5_5") (pintype "bidirectional"))
      (node (ref "J5") (pin "5") (pinfunction "5_5") (pintype "bidirectional"))
      (node (ref "J7") (pin "6") (pinfunction "6_6") (pintype "bidirectional"))
      (node (ref "LDO7") (pin "2") (pinfunction "GND_2") (pintype "bidirectional"))
      (node (ref "LDO7") (pin "DGND") (pinfunction "GND_DGND") (pintype "bidirectional"))
      (node (ref "LDO7") (pin "DGND2") (pinfunction "GND_DGND2") (pintype "bidirectional"))
      (node (ref "LDO7") (pin "DGND3") (pinfunction "GND_DGND3") (pintype "bidirectional"))
      (node (ref "R6A") (pin "2") (pinfunction "2_2") (pintype "passive"))
      (node (ref "R6B") (pin "2") (pinfunction "2_2") (pintype "passive"))
      (node (ref "R6D") (pin "2") (pinfunction "2_2") (pintype "passive"))
      (node (ref "R7A") (pin "2") (pinfunction "2_2") (pintype "passive"))
      (node (ref "R7B") (pin "2") (pinfunction "2_2") (pintype "passive"))
      (node (ref "R7D") (pin "2") (pinfunction "2_2") (pintype "passive"))
    )
    (net (code "29") (name "L+") (class "Default")
      (node (ref "R23O") (pin "1") (pinfunction "1_1") (pintype "passive"))
      (node (ref "R24O") (pin "1") (pinfunction "1_1") (pintype "passive"))
      (node (ref "R4") (pin "2") (pinfunction "2_2") (pintype "passive"))
    )
    (net (code "30") (name "L-") (class "Default")
      (node (ref "R25O") (pin "1") (pinfunction "1_1") (pintype "passive"))
      (node (ref "R26O") (pin "1") (pinfunction "1_1") (pintype "passive"))
      (node (ref "R3") (pin "2") (pinfunction "2_2") (pintype "passive"))
    )
    (net (code "31") (name "L_OUT") (class "Default")
      (node (ref "C21O1") (pin "1") (pinfunction "1_1") (pintype "passive"))
      (node (ref "C21O1") (pin "4") (pinfunction "1_4") (pintype "passive"))
      (node (ref "J3") (pin "2") (pinfunction "TIP_2") (pintype "bidirectional"))
      (node (ref "R20O2") (pin "2") (pinfunction "2_2") (pintype "passive"))
      (node (ref "Z5") (pin "1") (pinfunction "C_1") (pintype "passive"))
    )
    (net (code "32") (name "Net-(C1P-+)") (class "Default")
      (node (ref "C1P") (pin "1") (pinfunction "+_1") (pintype "bidirectional"))
      (node (ref "D10") (pin "1") (pinfunction "K_1") (pintype "bidirectional"))
      (node (ref "D9") (pin "1") (pinfunction "K_1") (pintype "bidirectional"))
      (node (ref "J6") (pin "4") (pinfunction "4_4") (pintype "bidirectional"))
    )
    (net (code "33") (name "Net-(C1P1-+)") (class "Default")
      (node (ref "C1P1") (pin "1") (pinfunction "+_1") (pintype "bidirectional"))
      (node (ref "D13") (pin "1") (pinfunction "K_1") (pintype "bidirectional"))
      (node (ref "D14") (pin "1") (pinfunction "K_1") (pintype "bidirectional"))
      (node (ref "J6") (pin "10") (pinfunction "10_10") (pintype "bidirectional"))
    )
    (net (code "34") (name "Net-(C1P2-+)") (class "Default")
      (node (ref "C1P2") (pin "1") (pinfunction "+_1") (pintype "bidirectional"))
      (node (ref "D17") (pin "1") (pinfunction "K_1") (pintype "bidirectional"))
      (node (ref "D18") (pin "1") (pinfunction "K_1") (pintype "bidirectional"))
      (node (ref "J4") (pin "8") (pinfunction "8_8") (pintype "bidirectional"))
    )
    (net (code "35") (name "Net-(C1P3-+)") (class "Default")
      (node (ref "C1P3") (pin "1") (pinfunction "+_1") (pintype "bidirectional"))
      (node (ref "D21") (pin "1") (pinfunction "K_1") (pintype "bidirectional"))
      (node (ref "D22") (pin "1") (pinfunction "K_1") (pintype "bidirectional"))
      (node (ref "J4") (pin "2") (pinfunction "2_2") (pintype "bidirectional"))
    )
    (net (code "36") (name "Net-(C2O-Pad1)") (class "Default")
      (node (ref "C2O") (pin "1") (pinfunction "1_1") (pintype "passive"))
      (node (ref "R17") (pin "2") (pinfunction "2_2") (pintype "passive"))
      (node (ref "SX1") (pin "6") (pinfunction "6_6") (pintype "passive"))
    )
    (net (code "37") (name "Net-(C2O-Pad2)") (class "Default")
      (node (ref "C2O") (pin "2") (pinfunction "2_2") (pintype "passive"))
      (node (ref "R3O") (pin "1") (pinfunction "1_1") (pintype "passive"))
      (node (ref "R8") (pin "2") (pinfunction "2_2") (pintype "passive"))
    )
    (net (code "38") (name "Net-(C2O1-Pad1)") (class "Default")
      (node (ref "C2O1") (pin "1") (pinfunction "1_1") (pintype "passive"))
      (node (ref "R18") (pin "1") (pinfunction "1_1") (pintype "passive"))
      (node (ref "SX2") (pin "6") (pinfunction "6_6") (pintype "passive"))
    )
    (net (code "39") (name "Net-(C2O1-Pad2)") (class "Default")
      (node (ref "C2O1") (pin "2") (pinfunction "2_2") (pintype "passive"))
      (node (ref "R14") (pin "2") (pinfunction "2_2") (pintype "passive"))
      (node (ref "R3O1") (pin "1") (pinfunction "1_1") (pintype "passive"))
    )
    (net (code "40") (name "Net-(C2P-+)") (class "Default")
      (node (ref "C2P") (pin "1") (pinfunction "+_1") (pintype "bidirectional"))
      (node (ref "J6") (pin "5") (pinfunction "5_5") (pintype "bidirectional"))
      (node (ref "R6P") (pin "2") (pinfunction "2_2") (pintype "passive"))
    )
    (net (code "41") (name "Net-(C2P1-+)") (class "Default")
      (node (ref "C2P1") (pin "1") (pinfunction "+_1") (pintype "bidirectional"))
      (node (ref "J6") (pin "11") (pinfunction "11_11") (pintype "bidirectional"))
      (node (ref "R6P1") (pin "2") (pinfunction "2_2") (pintype "passive"))
    )
    (net (code "42") (name "Net-(C2P2-+)") (class "Default")
      (node (ref "C2P2") (pin "1") (pinfunction "+_1") (pintype "bidirectional"))
      (node (ref "J4") (pin "7") (pinfunction "7_7") (pintype "bidirectional"))
      (node (ref "R6P2") (pin "2") (pinfunction "2_2") (pintype "passive"))
    )
    (net (code "43") (name "Net-(C2P3-+)") (class "Default")
      (node (ref "C2P3") (pin "1") (pinfunction "+_1") (pintype "bidirectional"))
      (node (ref "J4") (pin "1") (pinfunction "1_1") (pintype "bidirectional"))
      (node (ref "R6P3") (pin "2") (pinfunction "2_2") (pintype "passive"))
    )
    (net (code "44") (name "Net-(C4P-+)") (class "Default")
      (node (ref "C4P") (pin "1") (pinfunction "+_1") (pintype "bidirectional"))
      (node (ref "R2P") (pin "1") (pinfunction "1_1") (pintype "passive"))
      (node (ref "R3P") (pin "2") (pinfunction "2_2") (pintype "passive"))
      (node (ref "R4P") (pin "1") (pinfunction "1_1") (pintype "passive"))
      (node (ref "R5P") (pin "2") (pinfunction "2_2") (pintype "passive"))
    )
    (net (code "45") (name "Net-(C4P1-+)") (class "Default")
      (node (ref "C4P1") (pin "1") (pinfunction "+_1") (pintype "bidirectional"))
      (node (ref "R2P1") (pin "1") (pinfunction "1_1") (pintype "passive"))
      (node (ref "R3P1") (pin "2") (pinfunction "2_2") (pintype "passive"))
      (node (ref "R4P1") (pin "1") (pinfunction "1_1") (pintype "passive"))
      (node (ref "R5P1") (pin "2") (pinfunction "2_2") (pintype "passive"))
    )
    (net (code "46") (name "Net-(C11O-+)") (class "Default")
      (node (ref "C11O") (pin "1") (pinfunction "+_1") (pintype "passive"))
      (node (ref "J13") (pin "6") (pinfunction "6_6") (pintype "passive"))
    )
    (net (code "47") (name "Net-(C11O--)") (class "Default")
      (node (ref "C11O") (pin "2") (pinfunction "-_2") (pintype "passive"))
      (node (ref "R12O") (pin "2") (pinfunction "2_2") (pintype "passive"))
      (node (ref "R19O") (pin "2") (pinfunction "2_2") (pintype "passive"))
    )
    (net (code "48") (name "Net-(C12O-+)") (class "Default")
      (node (ref "C12O") (pin "1") (pinfunction "+_1") (pintype "passive"))
      (node (ref "J13") (pin "1") (pinfunction "1_1") (pintype "passive"))
    )
    (net (code "49") (name "Net-(C12O--)") (class "Default")
      (node (ref "C12O") (pin "2") (pinfunction "-_2") (pintype "passive"))
      (node (ref "R18O") (pin "2") (pinfunction "2_2") (pintype "passive"))
      (node (ref "R20O") (pin "1") (pinfunction "1_1") (pintype "passive"))
    )
    (net (code "50") (name "Net-(C13O-+)") (class "Default")
      (node (ref "C13O") (pin "1") (pinfunction "+_1") (pintype "passive"))
      (node (ref "J13") (pin "4") (pinfunction "4_4") (pintype "passive"))
    )
    (net (code "51") (name "Net-(C13O--)") (class "Default")
      (node (ref "C13O") (pin "2") (pinfunction "-_2") (pintype "passive"))
      (node (ref "R14O") (pin "2") (pinfunction "2_2") (pintype "passive"))
      (node (ref "R21O") (pin "2") (pinfunction "2_2") (pintype "passive"))
    )
    (net (code "52") (name "Net-(C14O-+)") (class "Default")
      (node (ref "C14O") (pin "1") (pinfunction "+_1") (pintype "passive"))
      (node (ref "J13") (pin "3") (pinfunction "3_3") (pintype "passive"))
    )
    (net (code "53") (name "Net-(C14O--)") (class "Default")
      (node (ref "C14O") (pin "2") (pinfunction "-_2") (pintype "passive"))
      (node (ref "R11O") (pin "1") (pinfunction "1_1") (pintype "passive"))
      (node (ref "R16O") (pin "2") (pinfunction "2_2") (pintype "passive"))
    )
    (net (code "54") (name "Net-(C15O-+)") (class "Default")
      (node (ref "C15O") (pin "1") (pinfunction "+_1") (pintype "passive"))
      (node (ref "J2") (pin "6") (pinfunction "6_6") (pintype "passive"))
    )
    (net (code "55") (name "Net-(C15O--)") (class "Default")
      (node (ref "C15O") (pin "2") (pinfunction "-_2") (pintype "passive"))
      (node (ref "R24O") (pin "2") (pinfunction "2_2") (pintype "passive"))
      (node (ref "R28O") (pin "2") (pinfunction "2_2") (pintype "passive"))
    )
    (net (code "56") (name "Net-(C24O-+)") (class "Default")
      (node (ref "C24O") (pin "1") (pinfunction "+_1") (pintype "passive"))
      (node (ref "J2") (pin "1") (pinfunction "1_1") (pintype "passive"))
    )
    (net (code "57") (name "Net-(C24O--)") (class "Default")
      (node (ref "C24O") (pin "2") (pinfunction "-_2") (pintype "passive"))
      (node (ref "R23O") (pin "2") (pinfunction "2_2") (pintype "passive"))
      (node (ref "R29O") (pin "1") (pinfunction "1_1") (pintype "passive"))
    )
    (net (code "58") (name "Net-(C25O-+)") (class "Default")
      (node (ref "C25O") (pin "1") (pinfunction "+_1") (pintype "passive"))
      (node (ref "J2") (pin "4") (pinfunction "4_4") (pintype "passive"))
    )
    (net (code "59") (name "Net-(C25O--)") (class "Default")
      (node (ref "C25O") (pin "2") (pinfunction "-_2") (pintype "passive"))
      (node (ref "R25O") (pin "2") (pinfunction "2_2") (pintype "passive"))
      (node (ref "R30O") (pin "2") (pinfunction "2_2") (pintype "passive"))
    )
    (net (code "60") (name "Net-(C26O-+)") (class "Default")
      (node (ref "C26O") (pin "1") (pinfunction "+_1") (pintype "passive"))
      (node (ref "J2") (pin "3") (pinfunction "3_3") (pintype "passive"))
    )
    (net (code "61") (name "Net-(C26O--)") (class "Default")
      (node (ref "C26O") (pin "2") (pinfunction "-_2") (pintype "passive"))
      (node (ref "R22O") (pin "1") (pinfunction "1_1") (pintype "passive"))
      (node (ref "R26O") (pin "2") (pinfunction "2_2") (pintype "passive"))
    )
    (net (code "62") (name "Net-(D1-A)") (class "Default")
      (node (ref "D1") (pin "2") (pinfunction "A_2") (pintype "passive"))
      (node (ref "R1") (pin "1") (pinfunction "1_1") (pintype "passive"))
      (node (ref "SX3") (pin "2") (pinfunction "2_2") (pintype "passive"))
    )
    (net (code "63") (name "Net-(D1-C)") (class "Default")
      (node (ref "D1") (pin "1") (pinfunction "C_1") (pintype "passive"))
      (node (ref "D2") (pin "1") (pinfunction "C_1") (pintype "passive"))
      (node (ref "SX3") (pin "3") (pinfunction "3_3") (pintype "passive"))
      (node (ref "SX3") (pin "8") (pinfunction "8_8") (pintype "passive"))
      (node (ref "U1") (pin "3") (pinfunction "IN_3") (pintype "input"))
    )
    (net (code "64") (name "Net-(D2-A)") (class "Default")
      (node (ref "D2") (pin "2") (pinfunction "A_2") (pintype "passive"))
      (node (ref "R2") (pin "1") (pinfunction "1_1") (pintype "passive"))
      (node (ref "SX3") (pin "7") (pinfunction "7_7") (pintype "passive"))
    )
    (net (code "65") (name "Net-(D3-A)") (class "Default")
      (node (ref "D3") (pin "2") (pinfunction "A_2") (pintype "passive"))
      (node (ref "R7") (pin "1") (pinfunction "1_1") (pintype "passive"))
      (node (ref "SX1") (pin "7") (pinfunction "7_7") (pintype "passive"))
    )
    (net (code "66") (name "Net-(D3-C)") (class "Default")
      (node (ref "C21O") (pin "2") (pinfunction "2_2") (pintype "passive"))
      (node (ref "C21O") (pin "3") (pinfunction "2_3") (pintype "passive"))
      (node (ref "D3") (pin "1") (pinfunction "C_1") (pintype "passive"))
      (node (ref "SX1") (pin "1") (pinfunction "1_1") (pintype "passive"))
      (node (ref "SX1") (pin "8") (pinfunction "8_8") (pintype "passive"))
    )
    (net (code "67") (name "Net-(D4-A)") (class "Default")
      (node (ref "D4") (pin "2") (pinfunction "A_2") (pintype "passive"))
      (node (ref "R3") (pin "1") (pinfunction "1_1") (pintype "passive"))
      (node (ref "SX4") (pin "2") (pinfunction "2_2") (pintype "passive"))
    )
    (net (code "68") (name "Net-(D4-C)") (class "Default")
      (node (ref "D4") (pin "1") (pinfunction "C_1") (pintype "passive"))
      (node (ref "D5") (pin "1") (pinfunction "C_1") (pintype "passive"))
      (node (ref "SX4") (pin "3") (pinfunction "3_3") (pintype "passive"))
      (node (ref "SX4") (pin "8") (pinfunction "8_8") (pintype "passive"))
      (node (ref "U2") (pin "3") (pinfunction "IN_3") (pintype "input"))
    )
    (net (code "69") (name "Net-(D5-A)") (class "Default")
      (node (ref "D5") (pin "2") (pinfunction "A_2") (pintype "passive"))
      (node (ref "R4") (pin "1") (pinfunction "1_1") (pintype "passive"))
      (node (ref "SX4") (pin "7") (pinfunction "7_7") (pintype "passive"))
    )
    (net (code "70") (name "Net-(D6-A)") (class "Default")
      (node (ref "D6") (pin "2") (pinfunction "A_2") (pintype "passive"))
      (node (ref "R13") (pin "1") (pinfunction "1_1") (pintype "passive"))
      (node (ref "SX2") (pin "7") (pinfunction "7_7") (pintype "passive"))
    )
    (net (code "71") (name "Net-(D6-C)") (class "Default")
      (node (ref "C21O1") (pin "2") (pinfunction "2_2") (pintype "passive"))
      (node (ref "C21O1") (pin "3") (pinfunction "2_3") (pintype "passive"))
      (node (ref "D6") (pin "1") (pinfunction "C_1") (pintype "passive"))
      (node (ref "SX2") (pin "1") (pinfunction "1_1") (pintype "passive"))
      (node (ref "SX2") (pin "8") (pinfunction "8_8") (pintype "passive"))
    )
    (net (code "72") (name "Net-(IC1-ILIM)") (class "Default")
      (node (ref "IC1") (pin "5") (pinfunction "ILIM_5") (pintype "bidirectional"))
      (node (ref "J1") (pin "2") (pinfunction "2_2") (pintype "bidirectional"))
      (node (ref "R6D") (pin "1") (pinfunction "1_1") (pintype "passive"))
    )
    (net (code "73") (name "Net-(IC1-PG)") (class "Default")
      (node (ref "IC1") (pin "4") (pinfunction "PG_4") (pintype "bidirectional"))
      (node (ref "J1") (pin "1") (pinfunction "1_1") (pintype "bidirectional"))
      (node (ref "R8D") (pin "2") (pinfunction "2_2") (pintype "passive"))
    )
    (net (code "74") (name "Net-(IC1-PGFB)") (class "Default")
      (node (ref "IC1") (pin "6") (pinfunction "PGFB_6") (pintype "bidirectional"))
      (node (ref "J1") (pin "3") (pinfunction "3_3") (pintype "bidirectional"))
    )
    (net (code "75") (name "Net-(IC1-SET)") (class "Default")
      (node (ref "C19D") (pin "1") (pinfunction "1_1") (pintype "passive"))
      (node (ref "IC1") (pin "7") (pinfunction "SET_7") (pintype "bidirectional"))
      (node (ref "J1") (pin "4") (pinfunction "4_4") (pintype "bidirectional"))
      (node (ref "R7D") (pin "1") (pinfunction "1_1") (pintype "passive"))
    )
    (net (code "76") (name "Net-(IC2-ILIM)") (class "Default")
      (node (ref "IC2") (pin "5") (pinfunction "ILIM_5") (pintype "bidirectional"))
      (node (ref "J5") (pin "2") (pinfunction "2_2") (pintype "bidirectional"))
      (node (ref "R6A") (pin "1") (pinfunction "1_1") (pintype "passive"))
    )
    (net (code "77") (name "Net-(IC2-PG)") (class "Default")
      (node (ref "IC2") (pin "4") (pinfunction "PG_4") (pintype "bidirectional"))
      (node (ref "J5") (pin "1") (pinfunction "1_1") (pintype "bidirectional"))
      (node (ref "R8A") (pin "2") (pinfunction "2_2") (pintype "passive"))
    )
    (net (code "78") (name "Net-(IC2-PGFB)") (class "Default")
      (node (ref "IC2") (pin "6") (pinfunction "PGFB_6") (pintype "bidirectional"))
      (node (ref "J5") (pin "3") (pinfunction "3_3") (pintype "bidirectional"))
    )
    (net (code "79") (name "Net-(IC2-SET)") (class "Default")
      (node (ref "C19A") (pin "1") (pinfunction "1_1") (pintype "passive"))
      (node (ref "IC2") (pin "7") (pinfunction "SET_7") (pintype "bidirectional"))
      (node (ref "J5") (pin "4") (pinfunction "4_4") (pintype "bidirectional"))
      (node (ref "R7A") (pin "1") (pinfunction "1_1") (pintype "passive"))
    )
    (net (code "80") (name "Net-(IC5-ILIM)") (class "Default")
      (node (ref "IC5") (pin "5") (pinfunction "ILIM_5") (pintype "bidirectional"))
      (node (ref "J17") (pin "2") (pinfunction "2_2") (pintype "bidirectional"))
      (node (ref "R6B") (pin "1") (pinfunction "1_1") (pintype "passive"))
    )
    (net (code "81") (name "Net-(IC5-PG)") (class "Default")
      (node (ref "IC5") (pin "4") (pinfunction "PG_4") (pintype "bidirectional"))
      (node (ref "J17") (pin "1") (pinfunction "1_1") (pintype "bidirectional"))
      (node (ref "R8B") (pin "2") (pinfunction "2_2") (pintype "passive"))
    )
    (net (code "82") (name "Net-(IC5-PGFB)") (class "Default")
      (node (ref "IC5") (pin "6") (pinfunction "PGFB_6") (pintype "bidirectional"))
      (node (ref "J17") (pin "3") (pinfunction "3_3") (pintype "bidirectional"))
    )
    (net (code "83") (name "Net-(IC5-SET)") (class "Default")
      (node (ref "C19B") (pin "1") (pinfunction "1_1") (pintype "passive"))
      (node (ref "IC5") (pin "7") (pinfunction "SET_7") (pintype "bidirectional"))
      (node (ref "J17") (pin "4") (pinfunction "4_4") (pintype "bidirectional"))
      (node (ref "R7B") (pin "1") (pinfunction "1_1") (pintype "passive"))
    )
    (net (code "84") (name "Net-(IC6-ILIM)") (class "Default")
      (node (ref "IC6") (pin "5") (pinfunction "ILIM_5") (pintype "bidirectional"))
      (node (ref "J8") (pin "2") (pinfunction "2_2") (pintype "bidirectional"))
      (node (ref "R6B2") (pin "1") (pinfunction "1_1") (pintype "passive"))
    )
    (net (code "85") (name "Net-(IC6-PG)") (class "Default")
      (node (ref "IC6") (pin "4") (pinfunction "PG_4") (pintype "bidirectional"))
      (node (ref "J8") (pin "1") (pinfunction "1_1") (pintype "bidirectional"))
      (node (ref "R8B2") (pin "2") (pinfunction "2_2") (pintype "passive"))
    )
    (net (code "86") (name "Net-(IC6-PGFB)") (class "Default")
      (node (ref "IC6") (pin "6") (pinfunction "PGFB_6") (pintype "bidirectional"))
      (node (ref "J8") (pin "3") (pinfunction "3_3") (pintype "bidirectional"))
    )
    (net (code "87") (name "Net-(IC6-SET)") (class "Default")
      (node (ref "C19B2") (pin "1") (pinfunction "1_1") (pintype "passive"))
      (node (ref "IC6") (pin "7") (pinfunction "SET_7") (pintype "bidirectional"))
      (node (ref "J8") (pin "4") (pinfunction "4_4") (pintype "bidirectional"))
      (node (ref "R7B2") (pin "1") (pinfunction "1_1") (pintype "passive"))
    )
    (net (code "88") (name "Net-(IC8-ILIM)") (class "Default")
      (node (ref "IC8") (pin "5") (pinfunction "ILIM_5") (pintype "bidirectional"))
      (node (ref "J10") (pin "2") (pinfunction "2_2") (pintype "bidirectional"))
      (node (ref "R6B4") (pin "1") (pinfunction "1_1") (pintype "passive"))
    )
    (net (code "89") (name "Net-(IC8-PG)") (class "Default")
      (node (ref "IC8") (pin "4") (pinfunction "PG_4") (pintype "bidirectional"))
      (node (ref "J10") (pin "1") (pinfunction "1_1") (pintype "bidirectional"))
      (node (ref "R8B4") (pin "2") (pinfunction "2_2") (pintype "passive"))
    )
    (net (code "90") (name "Net-(IC8-PGFB)") (class "Default")
      (node (ref "IC8") (pin "6") (pinfunction "PGFB_6") (pintype "bidirectional"))
      (node (ref "J10") (pin "3") (pinfunction "3_3") (pintype "bidirectional"))
    )
    (net (code "91") (name "Net-(IC8-SET)") (class "Default")
      (node (ref "C19B4") (pin "1") (pinfunction "1_1") (pintype "passive"))
      (node (ref "IC8") (pin "7") (pinfunction "SET_7") (pintype "bidirectional"))
      (node (ref "J10") (pin "4") (pinfunction "4_4") (pintype "bidirectional"))
      (node (ref "R7B4") (pin "1") (pinfunction "1_1") (pintype "passive"))
    )
    (net (code "92") (name "Net-(IC10-ILIM)") (class "Default")
      (node (ref "IC10") (pin "5") (pinfunction "ILIM_5") (pintype "bidirectional"))
      (node (ref "J12") (pin "2") (pinfunction "2_2") (pintype "bidirectional"))
      (node (ref "R6B6") (pin "1") (pinfunction "1_1") (pintype "passive"))
    )
    (net (code "93") (name "Net-(IC10-PG)") (class "Default")
      (node (ref "IC10") (pin "4") (pinfunction "PG_4") (pintype "bidirectional"))
      (node (ref "J12") (pin "1") (pinfunction "1_1") (pintype "bidirectional"))
      (node (ref "R8B6") (pin "2") (pinfunction "2_2") (pintype "passive"))
    )
    (net (code "94") (name "Net-(IC10-PGFB)") (class "Default")
      (node (ref "IC10") (pin "6") (pinfunction "PGFB_6") (pintype "bidirectional"))
      (node (ref "J12") (pin "3") (pinfunction "3_3") (pintype "bidirectional"))
    )
    (net (code "95") (name "Net-(IC10-SET)") (class "Default")
      (node (ref "C19B6") (pin "1") (pinfunction "1_1") (pintype "passive"))
      (node (ref "IC10") (pin "7") (pinfunction "SET_7") (pintype "bidirectional"))
      (node (ref "J12") (pin "4") (pinfunction "4_4") (pintype "bidirectional"))
      (node (ref "R7B6") (pin "1") (pinfunction "1_1") (pintype "passive"))
    )
    (net (code "96") (name "Net-(R5-Pad1)") (class "Default")
      (node (ref "R5") (pin "1") (pinfunction "1_1") (pintype "passive"))
      (node (ref "SX3") (pin "1") (pinfunction "1_1") (pintype "passive"))
    )
    (net (code "97") (name "Net-(R11-Pad1)") (class "Default")
      (node (ref "R11") (pin "1") (pinfunction "1_1") (pintype "passive"))
      (node (ref "SX4") (pin "1") (pinfunction "1_1") (pintype "passive"))
    )
    (net (code "98") (name "Net-(R13-Pad2)") (class "Default")
      (node (ref "R13") (pin "2") (pinfunction "2_2") (pintype "passive"))
      (node (ref "R20") (pin "2") (pinfunction "2_2") (pintype "passive"))
      (node (ref "SX4") (pin "6") (pinfunction "6_6") (pintype "passive"))
    )
    (net (code "99") (name "Net-(R19-Pad1)") (class "Default")
      (node (ref "R19") (pin "1") (pinfunction "1_1") (pintype "passive"))
      (node (ref "R7") (pin "2") (pinfunction "2_2") (pintype "passive"))
      (node (ref "SX3") (pin "6") (pinfunction "6_6") (pintype "passive"))
    )
    (net (code "100") (name "Net-(U1-OUT)") (class "Default")
      (node (ref "R10") (pin "2") (pinfunction "2_2") (pintype "passive"))
      (node (ref "U1") (pin "2") (pinfunction "OUT_2") (pintype "passive"))
    )
    (net (code "101") (name "Net-(U2-OUT)") (class "Default")
      (node (ref "R16") (pin "2") (pinfunction "2_2") (pintype "passive"))
      (node (ref "U2") (pin "2") (pinfunction "OUT_2") (pintype "passive"))
    )
    (net (code "102") (name "Net-(Z1-A)") (class "Default")
      (node (ref "Z1") (pin "2") (pinfunction "A_2") (pintype "passive"))
      (node (ref "Z2") (pin "2") (pinfunction "A_2") (pintype "passive"))
    )
    (net (code "103") (name "Net-(Z3-A)") (class "Default")
      (node (ref "R8") (pin "1") (pinfunction "1_1") (pintype "passive"))
      (node (ref "SX1") (pin "2") (pinfunction "2_2") (pintype "passive"))
      (node (ref "Z3") (pin "2") (pinfunction "A_2") (pintype "passive"))
    )
    (net (code "104") (name "Net-(Z3-C)") (class "Default")
      (node (ref "R9") (pin "2") (pinfunction "2_2") (pintype "passive"))
      (node (ref "SX1") (pin "3") (pinfunction "3_3") (pintype "passive"))
      (node (ref "Z3") (pin "1") (pinfunction "C_1") (pintype "passive"))
    )
    (net (code "105") (name "Net-(Z4-A)") (class "Default")
      (node (ref "R14") (pin "1") (pinfunction "1_1") (pintype "passive"))
      (node (ref "SX2") (pin "2") (pinfunction "2_2") (pintype "passive"))
      (node (ref "Z4") (pin "2") (pinfunction "A_2") (pintype "passive"))
    )
    (net (code "106") (name "Net-(Z4-C)") (class "Default")
      (node (ref "R15") (pin "2") (pinfunction "2_2") (pintype "passive"))
      (node (ref "SX2") (pin "3") (pinfunction "3_3") (pintype "passive"))
      (node (ref "Z4") (pin "1") (pinfunction "C_1") (pintype "passive"))
    )
    (net (code "107") (name "Net-(Z5-A)") (class "Default")
      (node (ref "Z5") (pin "2") (pinfunction "A_2") (pintype "passive"))
      (node (ref "Z6") (pin "2") (pinfunction "A_2") (pintype "passive"))
    )
    (net (code "108") (name "R+") (class "Default")
      (node (ref "R12O") (pin "1") (pinfunction "1_1") (pintype "passive"))
      (node (ref "R18O") (pin "1") (pinfunction "1_1") (pintype "passive"))
      (node (ref "R2") (pin "2") (pinfunction "2_2") (pintype "passive"))
    )
    (net (code "109") (name "R-") (class "Default")
      (node (ref "R1") (pin "2") (pinfunction "2_2") (pintype "passive"))
      (node (ref "R14O") (pin "1") (pinfunction "1_1") (pintype "passive"))
      (node (ref "R16O") (pin "1") (pinfunction "1_1") (pintype "passive"))
    )
    (net (code "110") (name "R_OUT") (class "Default")
      (node (ref "C21O") (pin "1") (pinfunction "1_1") (pintype "passive"))
      (node (ref "C21O") (pin "4") (pinfunction "1_4") (pintype "passive"))
      (node (ref "J3") (pin "3") (pinfunction "RING_3") (pintype "bidirectional"))
      (node (ref "R20O1") (pin "2") (pinfunction "2_2") (pintype "passive"))
      (node (ref "Z2") (pin "1") (pinfunction "C_1") (pintype "passive"))
    )
    (net (code "111") (name "VCC{slash}1") (class "Default")
      (node (ref "C20B2") (pin "1") (pinfunction "1_1") (pintype "passive"))
      (node (ref "C20B4") (pin "1") (pinfunction "1_1") (pintype "passive"))
      (node (ref "C20B6") (pin "1") (pinfunction "1_1") (pintype "passive"))
      (node (ref "C21B2") (pin "1") (pinfunction "1_1") (pintype "passive"))
      (node (ref "C21B4") (pin "1") (pinfunction "1_1") (pintype "passive"))
      (node (ref "C21B6") (pin "1") (pinfunction "1_1") (pintype "passive"))
      (node (ref "C3P3") (pin "1") (pinfunction "+_1") (pintype "bidirectional"))
      (node (ref "C5P3") (pin "1") (pinfunction "+_1") (pintype "bidirectional"))
      (node (ref "C6") (pin "1") (pinfunction "+_1") (pintype "bidirectional"))
      (node (ref "C6P3") (pin "1") (pinfunction "+_1") (pintype "bidirectional"))
      (node (ref "C7P3") (pin "1") (pinfunction "+_1") (pintype "bidirectional"))
      (node (ref "IC10") (pin "1") (pinfunction "IN_1") (pintype "bidirectional"))
      (node (ref "IC10") (pin "2") (pinfunction "IN_2") (pintype "bidirectional"))
      (node (ref "IC10") (pin "3") (pinfunction "EN/UV_3") (pintype "bidirectional"))
      (node (ref "IC4") (pin "3") (pinfunction "IN_3") (pintype "input"))
      (node (ref "IC6") (pin "1") (pinfunction "IN_1") (pintype "bidirectional"))
      (node (ref "IC6") (pin "2") (pinfunction "IN_2") (pintype "bidirectional"))
      (node (ref "IC6") (pin "3") (pinfunction "EN/UV_3") (pintype "bidirectional"))
      (node (ref "IC8") (pin "1") (pinfunction "IN_1") (pintype "bidirectional"))
      (node (ref "IC8") (pin "2") (pinfunction "IN_2") (pintype "bidirectional"))
      (node (ref "IC8") (pin "3") (pinfunction "EN/UV_3") (pintype "bidirectional"))
      (node (ref "J10") (pin "7") (pinfunction "7_7") (pintype "bidirectional"))
      (node (ref "J10") (pin "8") (pinfunction "8_8") (pintype "bidirectional"))
      (node (ref "J12") (pin "7") (pinfunction "7_7") (pintype "bidirectional"))
      (node (ref "J12") (pin "8") (pinfunction "8_8") (pintype "bidirectional"))
      (node (ref "J8") (pin "7") (pinfunction "7_7") (pintype "bidirectional"))
      (node (ref "J8") (pin "8") (pinfunction "8_8") (pintype "bidirectional"))
      (node (ref "R6P3") (pin "1") (pinfunction "1_1") (pintype "passive"))
      (node (ref "R8B2") (pin "1") (pinfunction "1_1") (pintype "passive"))
      (node (ref "R8B4") (pin "1") (pinfunction "1_1") (pintype "passive"))
      (node (ref "R8B6") (pin "1") (pinfunction "1_1") (pintype "passive"))
    )
    (net (code "112") (name "VCC{slash}2") (class "Default")
      (node (ref "C20B") (pin "1") (pinfunction "1_1") (pintype "passive"))
      (node (ref "C20D") (pin "1") (pinfunction "1_1") (pintype "passive"))
      (node (ref "C21B") (pin "1") (pinfunction "1_1") (pintype "passive"))
      (node (ref "C21D") (pin "1") (pinfunction "1_1") (pintype "passive"))
      (node (ref "C3P1") (pin "1") (pinfunction "+_1") (pintype "bidirectional"))
      (node (ref "C5P1") (pin "1") (pinfunction "+_1") (pintype "bidirectional"))
      (node (ref "C6P1") (pin "1") (pinfunction "+_1") (pintype "bidirectional"))
      (node (ref "C7") (pin "1") (pinfunction "+_1") (pintype "bidirectional"))
      (node (ref "C7P1") (pin "1") (pinfunction "+_1") (pintype "bidirectional"))
      (node (ref "IC1") (pin "1") (pinfunction "IN_1") (pintype "bidirectional"))
      (node (ref "IC1") (pin "2") (pinfunction "IN_2") (pintype "bidirectional"))
      (node (ref "IC1") (pin "3") (pinfunction "EN/UV_3") (pintype "bidirectional"))
      (node (ref "IC3") (pin "3") (pinfunction "IN_3") (pintype "input"))
      (node (ref "IC5") (pin "1") (pinfunction "IN_1") (pintype "bidirectional"))
      (node (ref "IC5") (pin "2") (pinfunction "IN_2") (pintype "bidirectional"))
      (node (ref "IC5") (pin "3") (pinfunction "EN/UV_3") (pintype "bidirectional"))
      (node (ref "J1") (pin "7") (pinfunction "7_7") (pintype "bidirectional"))
      (node (ref "J1") (pin "8") (pinfunction "8_8") (pintype "bidirectional"))
      (node (ref "J17") (pin "7") (pinfunction "7_7") (pintype "bidirectional"))
      (node (ref "J17") (pin "8") (pinfunction "8_8") (pintype "bidirectional"))
      (node (ref "R6P1") (pin "1") (pinfunction "1_1") (pintype "passive"))
      (node (ref "R8B") (pin "1") (pinfunction "1_1") (pintype "passive"))
      (node (ref "R8D") (pin "1") (pinfunction "1_1") (pintype "passive"))
    )
    (net (code "113") (name "unconnected-(J4-Pad11)") (class "Default")
      (node (ref "J4") (pin "11") (pinfunction "11_11") (pintype "bidirectional"))
    )
    (net (code "114") (name "unconnected-(J6-Pad1)") (class "Default")
      (node (ref "J6") (pin "1") (pinfunction "1_1") (pintype "bidirectional"))
    )
    (net (code "115") (name "unconnected-(LDO1-NC-Pad4)") (class "Default")
      (node (ref "LDO1") (pin "4") (pinfunction "NC_4") (pintype "no_connect"))
    )
    (net (code "116") (name "unconnected-(LDO7-NC-Pad4)") (class "Default")
      (node (ref "LDO7") (pin "4") (pinfunction "NC_4") (pintype "no_connect"))
    )
    (net (code "117") (name "unconnected-(SX1-Pad9)") (class "Default")
      (node (ref "SX1") (pin "9") (pinfunction "9_9") (pintype "passive"))
    )
    (net (code "118") (name "unconnected-(SX2-Pad9)") (class "Default")
      (node (ref "SX2") (pin "9") (pinfunction "9_9") (pintype "passive"))
    )
    (net (code "119") (name "unconnected-(SX3-Pad9)") (class "Default")
      (node (ref "SX3") (pin "9") (pinfunction "9_9") (pintype "passive"))
    )
    (net (code "120") (name "unconnected-(SX4-Pad9)") (class "Default")
      (node (ref "SX4") (pin "9") (pinfunction "9_9") (pintype "passive"))
    )
  )
)
